# JETSON.net
KiCad netlist of a schematic drawn in Altium Designer
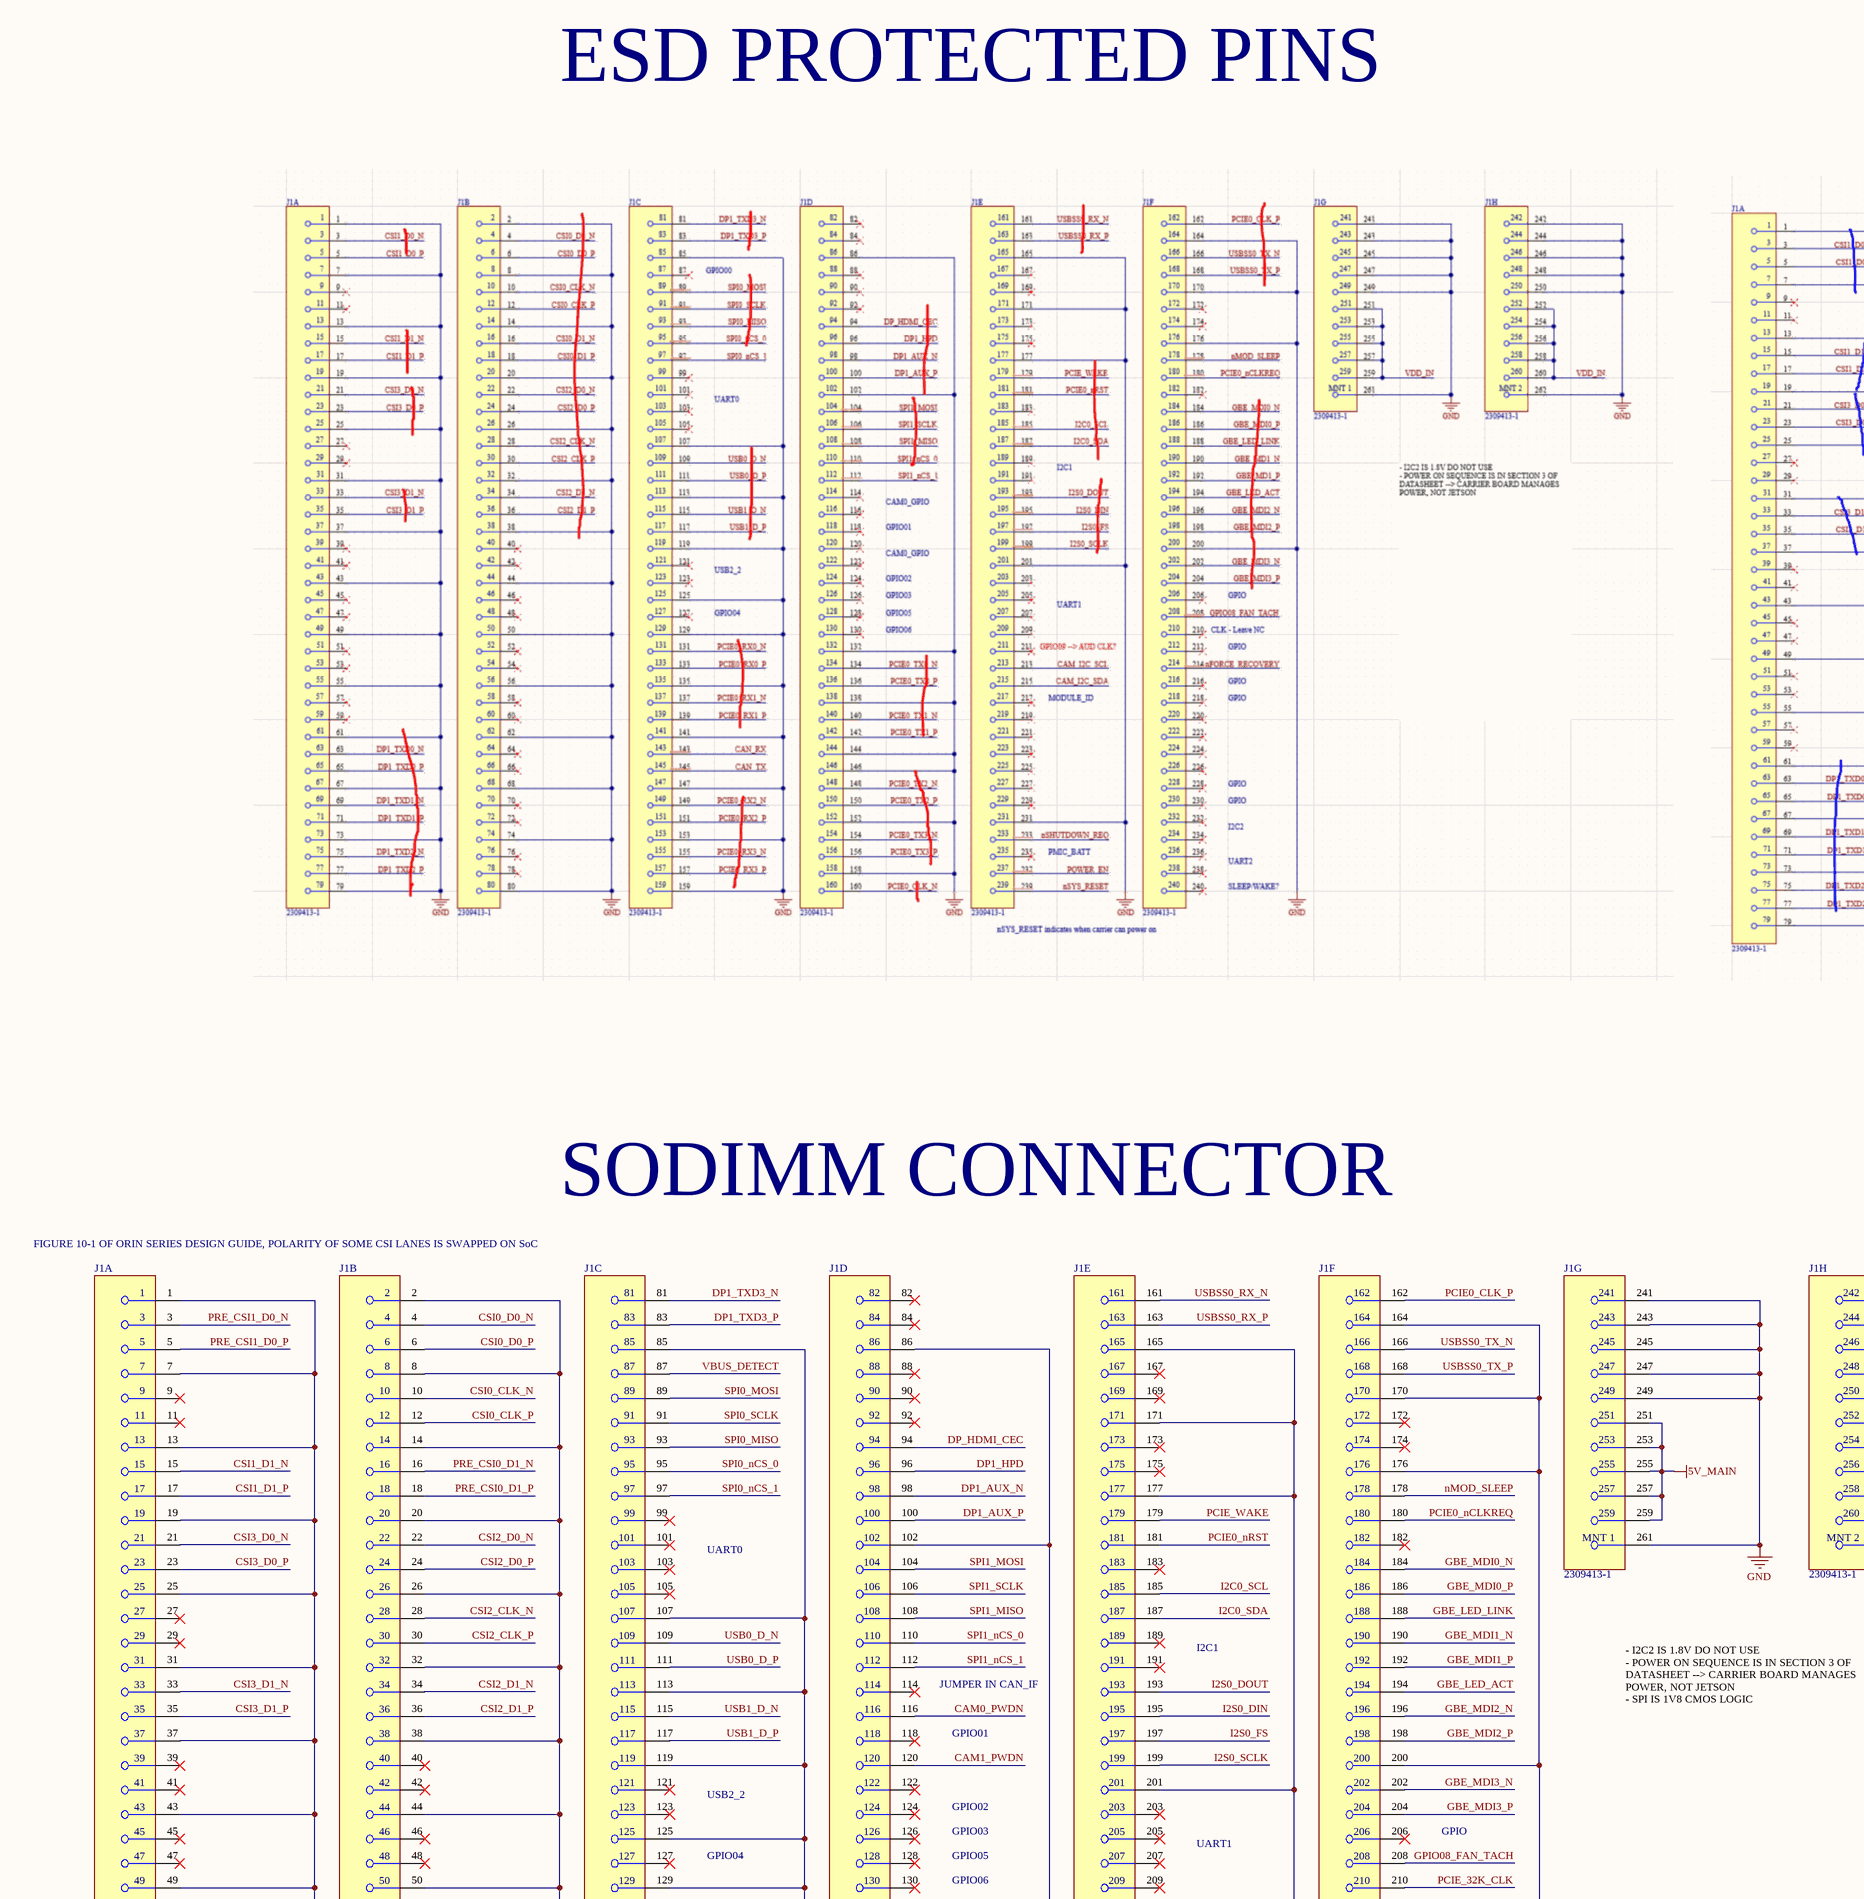
[diagram p0: JETSON.SchDoc, top left]
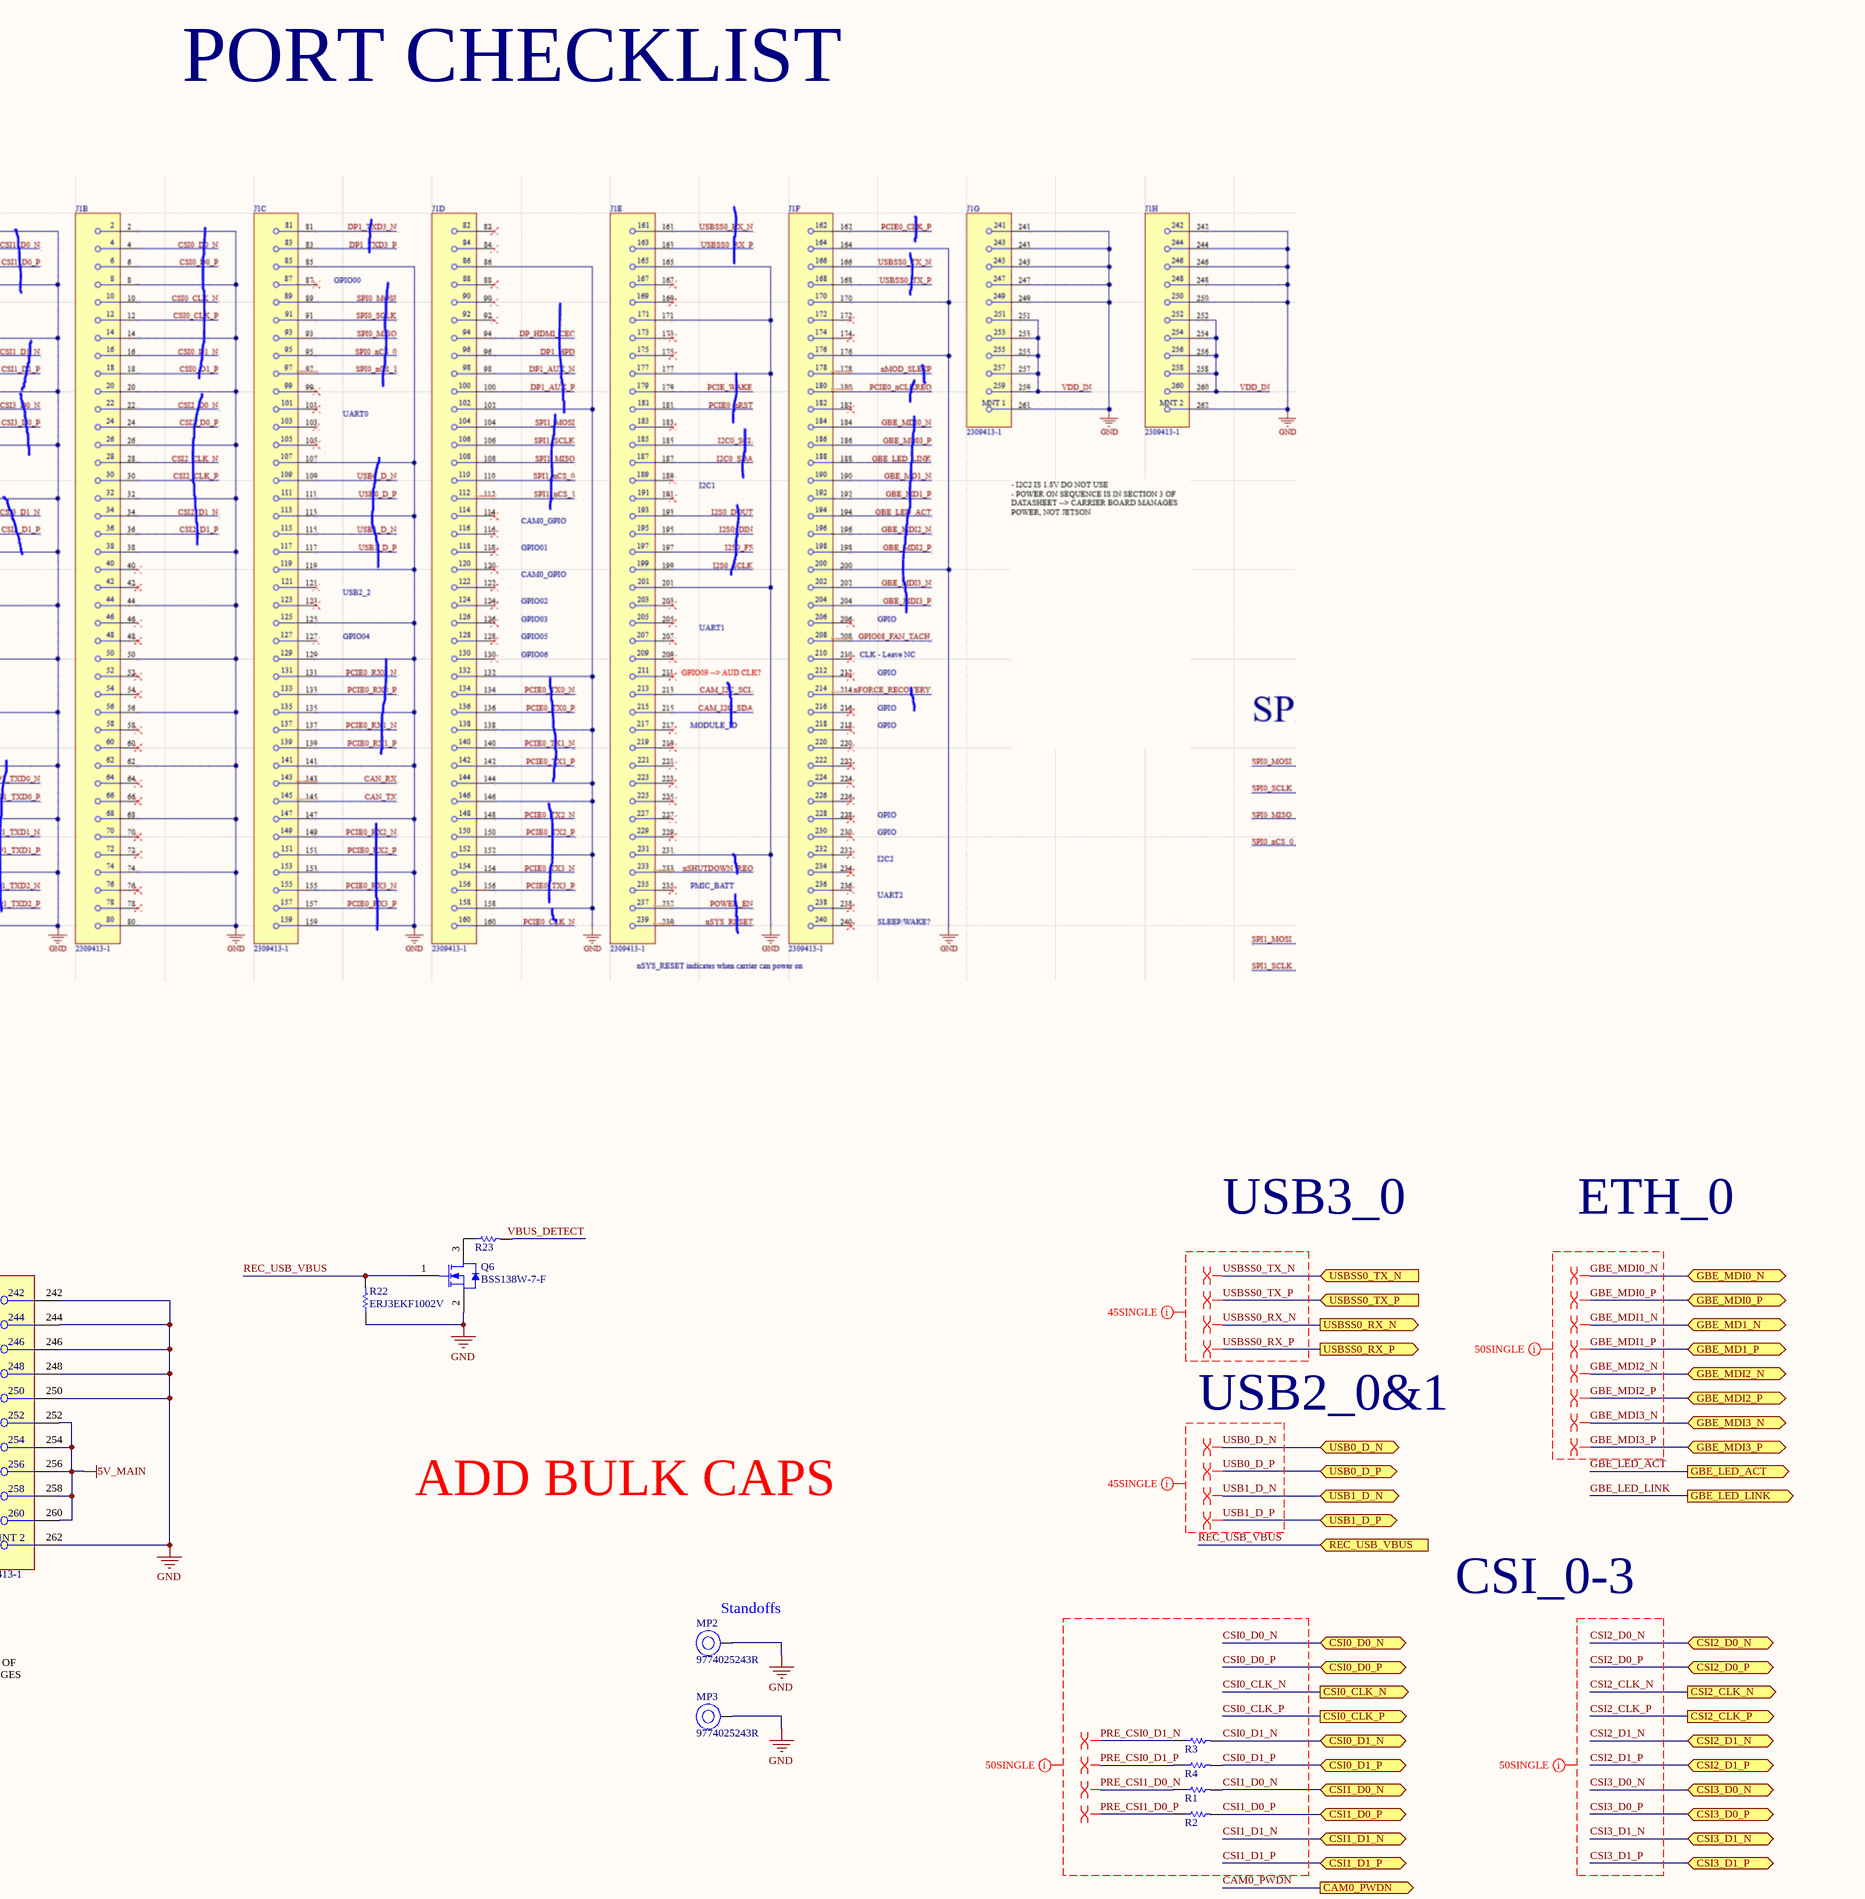
[diagram p1: JETSON.SchDoc, top right]
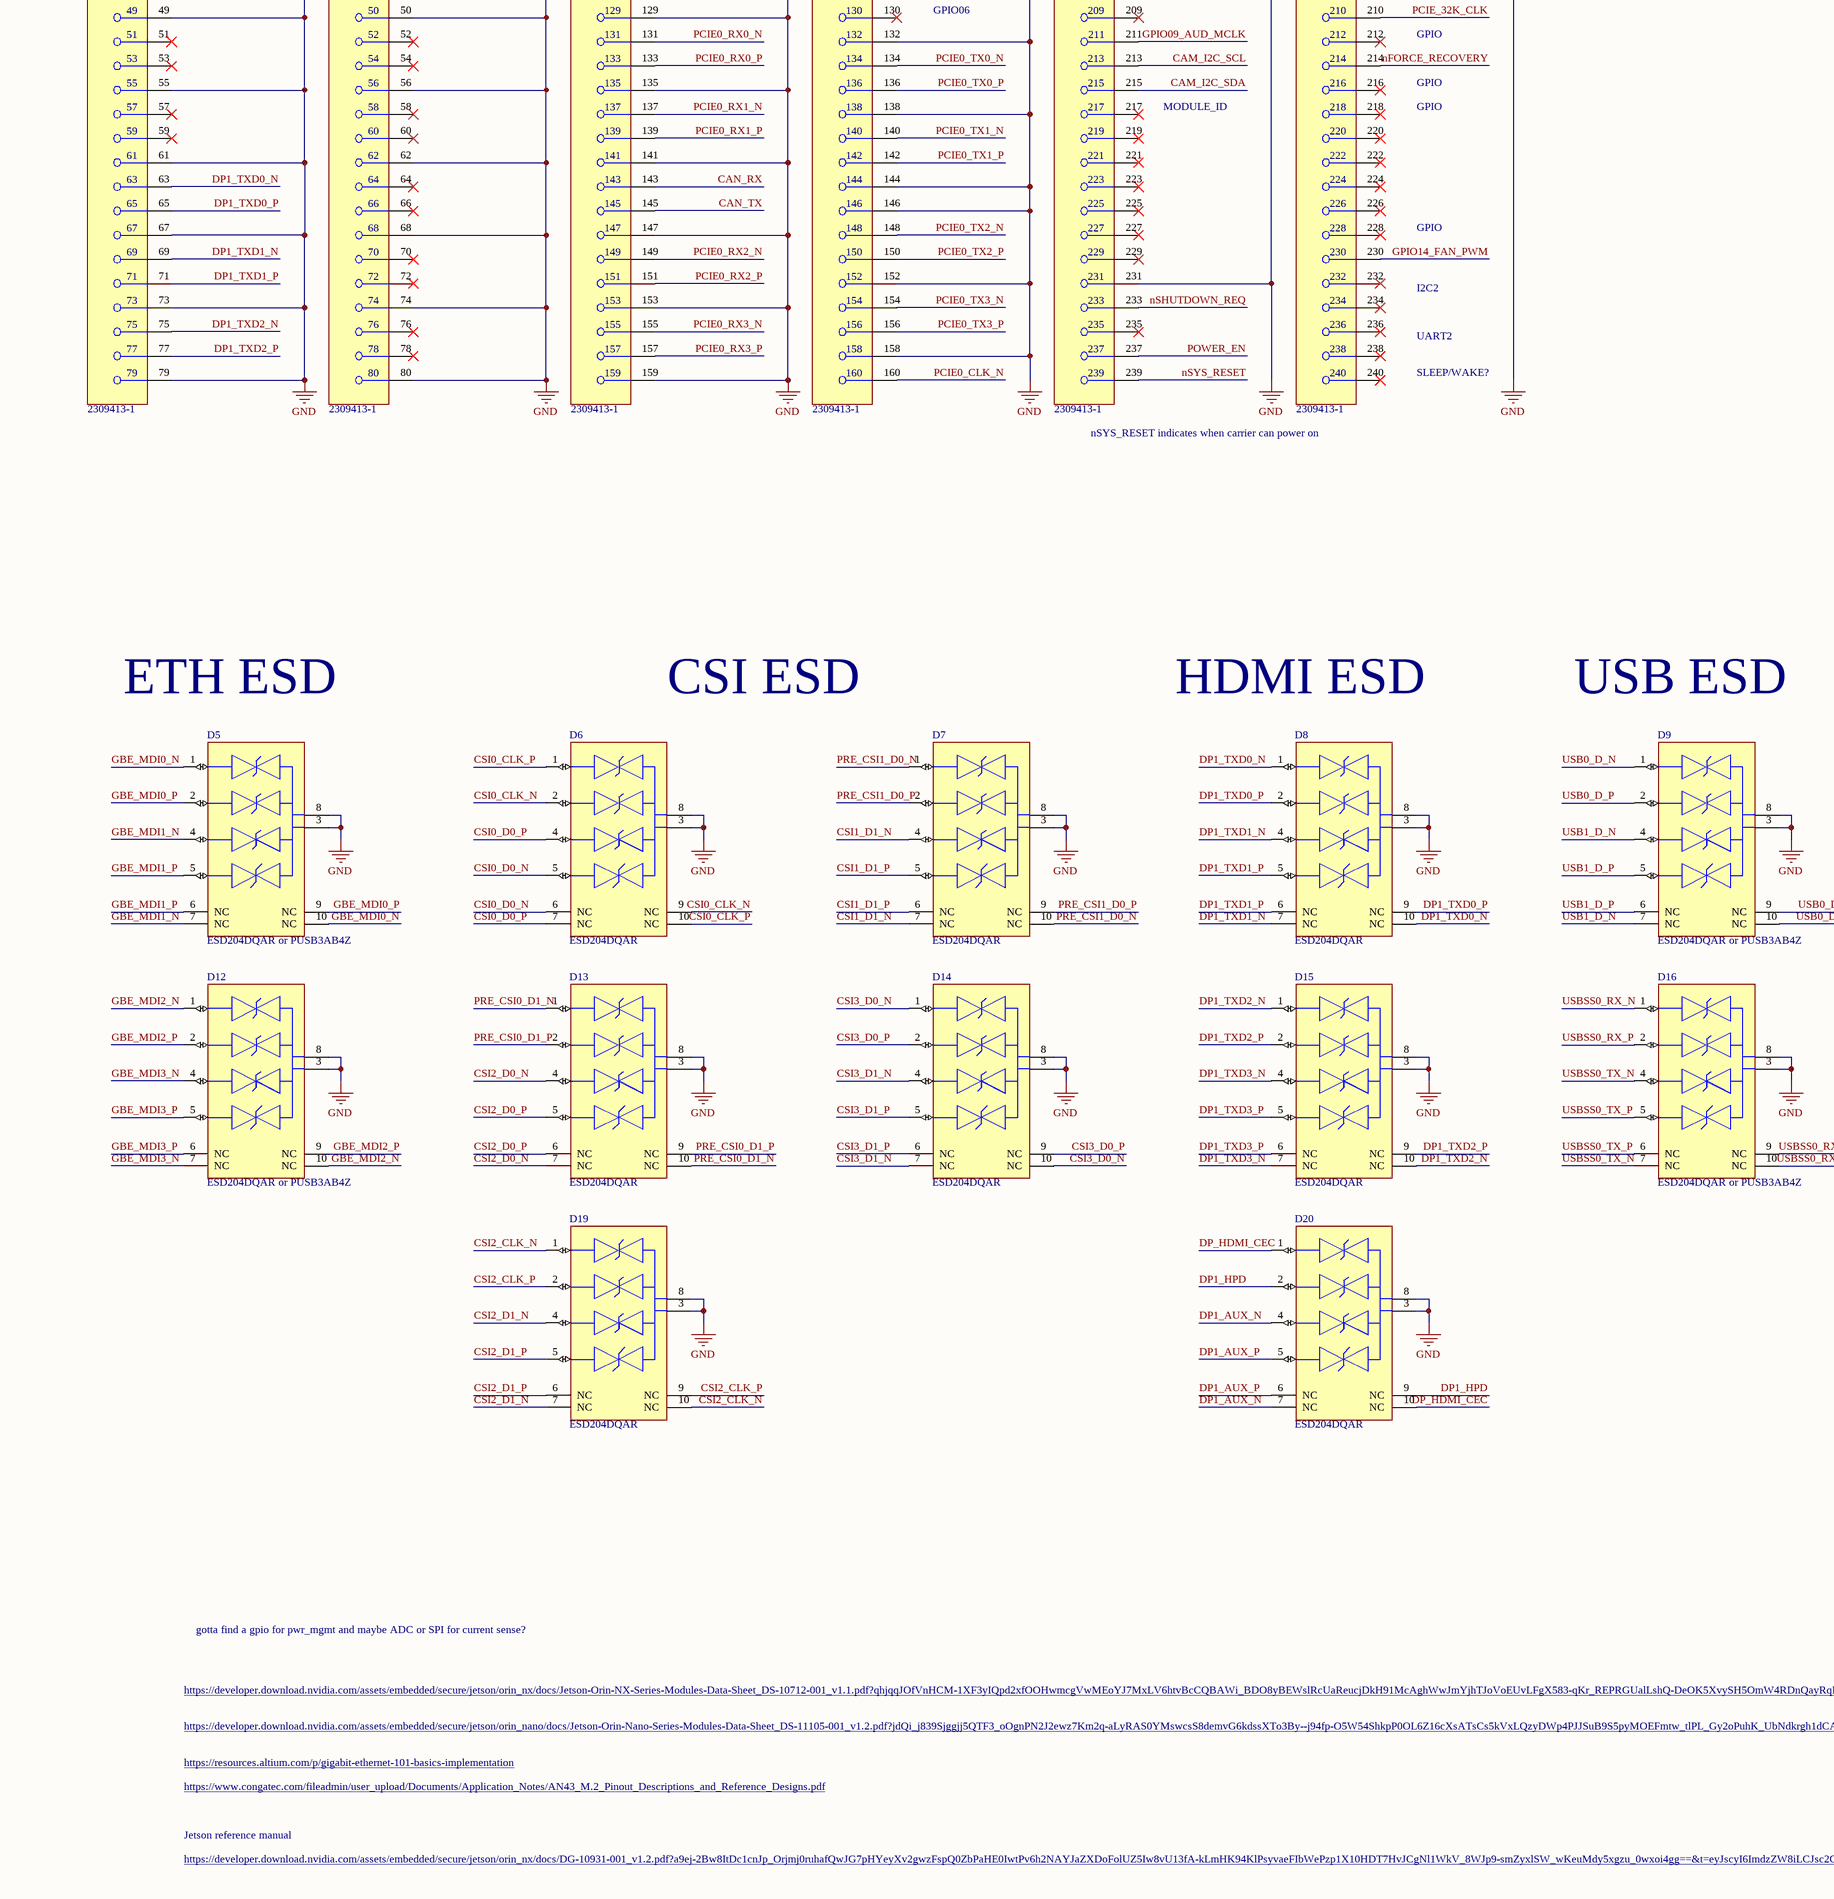
[diagram p2: JETSON.SchDoc, bottom left]
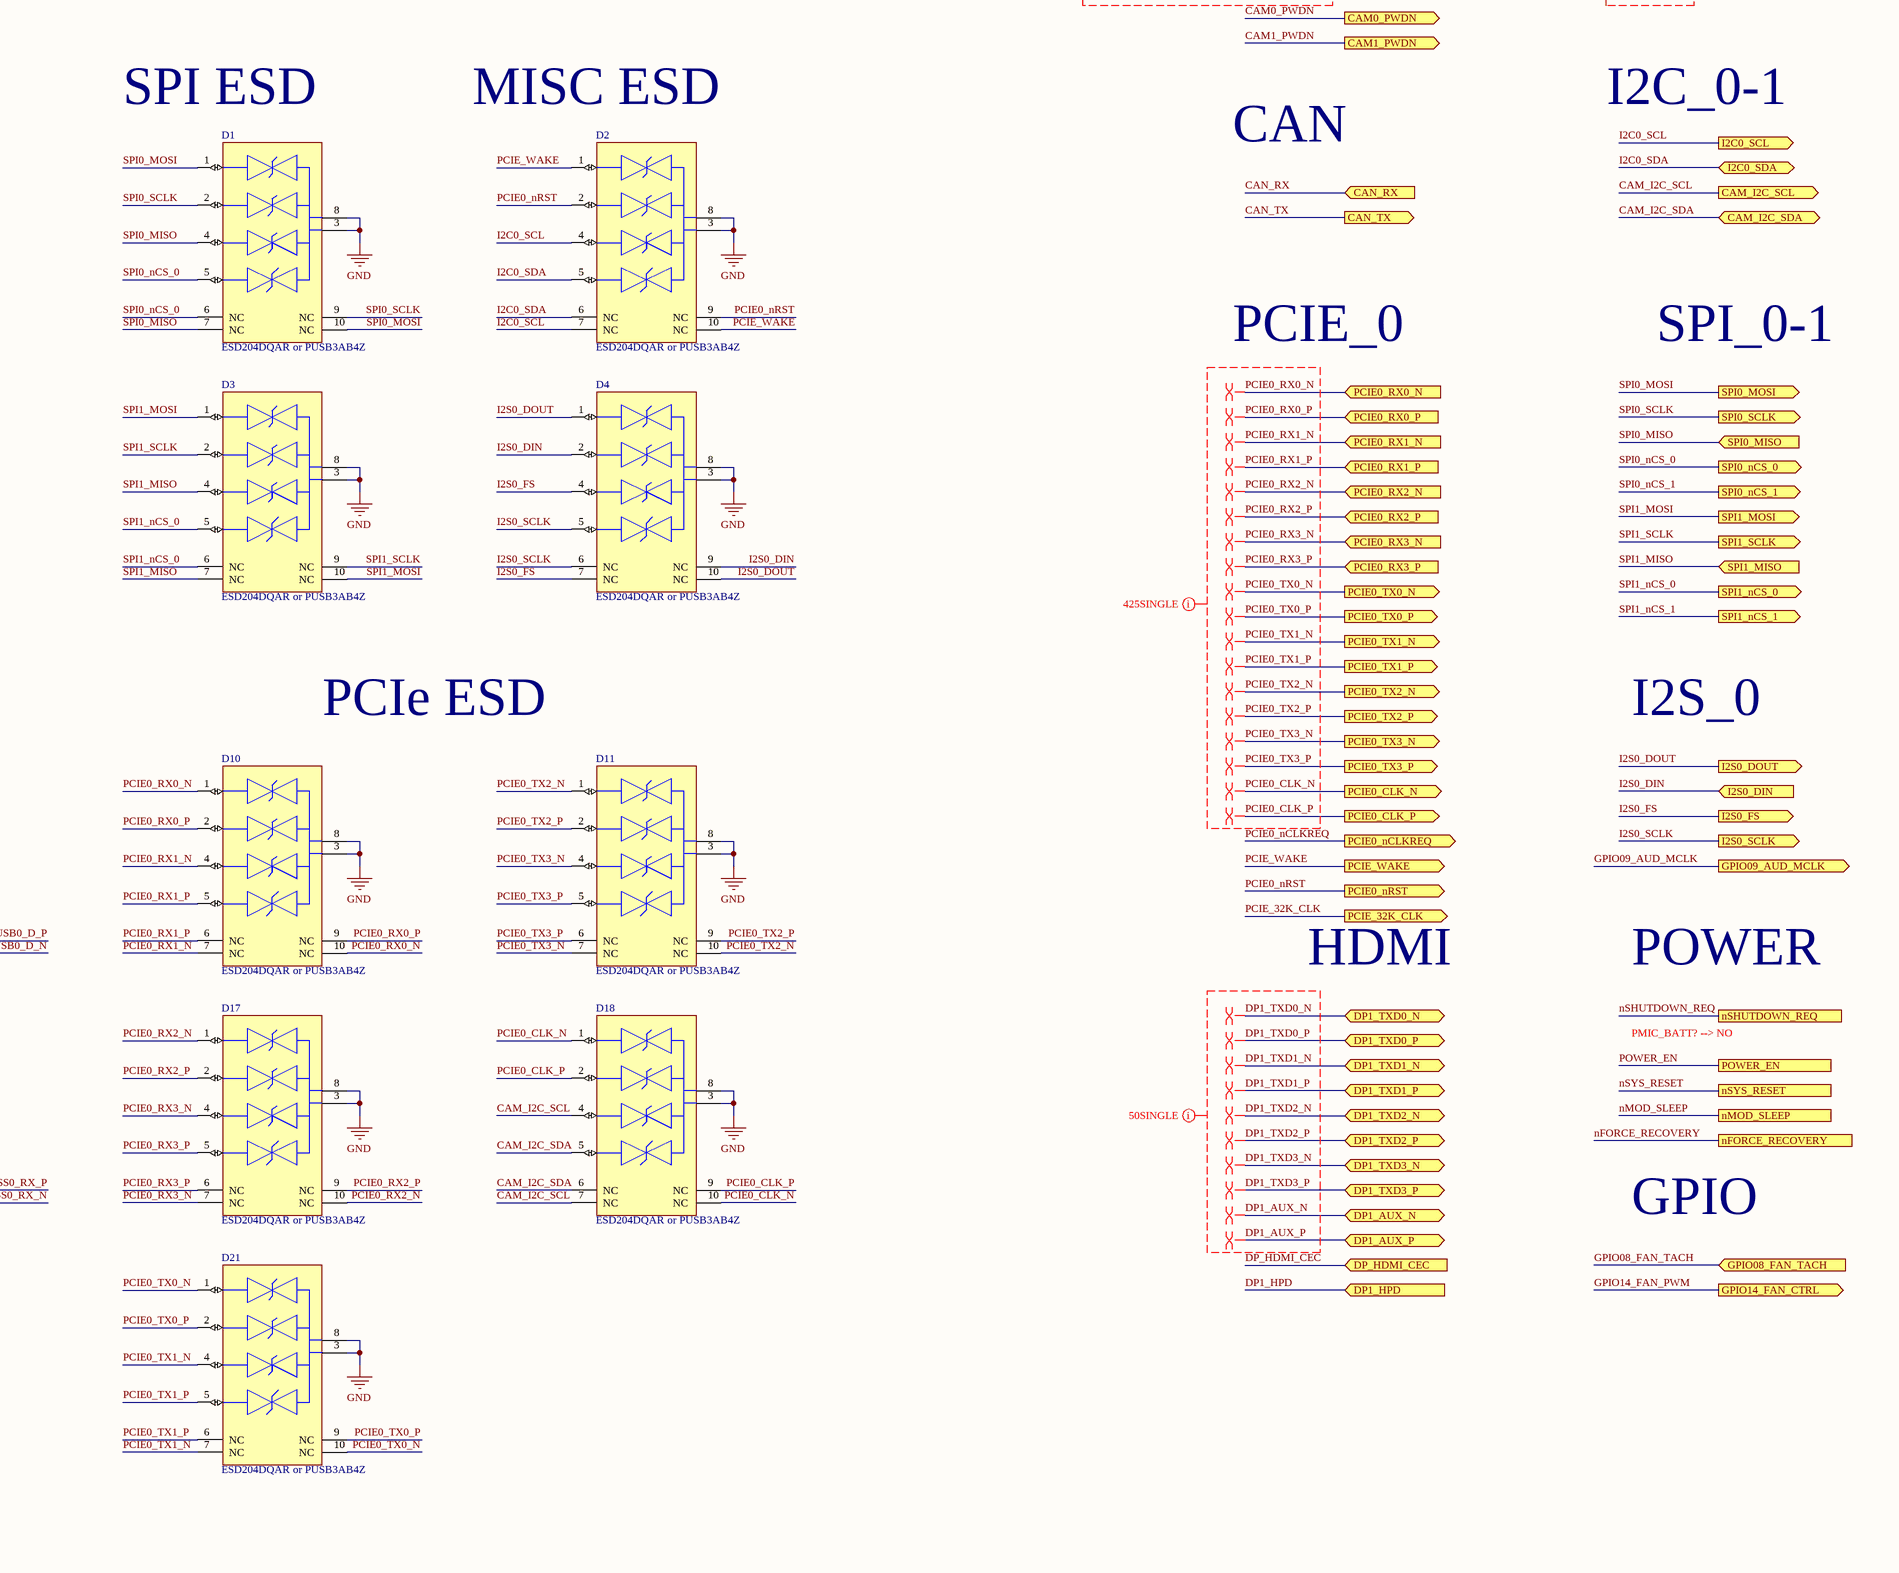
[diagram p3: JETSON.SchDoc, bottom right]

(export (version "E")
  (design (tool "Eeschema 10.0.6"))
  (components
    (comp (ref "D1")
      (value "ESD204DQAR or PUSB3AB4Z")
      (footprint "FP-DQA0010A-MFG")
      (description "4-CHANNEL LOW-CAPACITANCE SURGE")
      (fields
        (field (name "MANUFACTURER") "Texas Instruments")
        (field (name "OCTOPART") "https://octopart.com/esd204dqar-texas+instruments-89917476")
      )
      (libsource (lib "Altium Content Vault") (part "1465e58c1818c7767b55926832f0bf5"))
    )
    (comp (ref "D2")
      (value "ESD204DQAR or PUSB3AB4Z")
      (footprint "FP-DQA0010A-MFG")
      (description "4-CHANNEL LOW-CAPACITANCE SURGE")
      (fields
        (field (name "MANUFACTURER") "Texas Instruments")
        (field (name "OCTOPART") "https://octopart.com/esd204dqar-texas+instruments-89917476")
      )
      (libsource (lib "Altium Content Vault") (part "1465e58c1818c7767b55926832f0bf5"))
    )
    (comp (ref "D3")
      (value "ESD204DQAR or PUSB3AB4Z")
      (footprint "FP-DQA0010A-MFG")
      (description "4-CHANNEL LOW-CAPACITANCE SURGE")
      (fields
        (field (name "MANUFACTURER") "Texas Instruments")
        (field (name "OCTOPART") "https://octopart.com/esd204dqar-texas+instruments-89917476")
      )
      (libsource (lib "Altium Content Vault") (part "1465e58c1818c7767b55926832f0bf5"))
    )
    (comp (ref "D4")
      (value "ESD204DQAR or PUSB3AB4Z")
      (footprint "FP-DQA0010A-MFG")
      (description "4-CHANNEL LOW-CAPACITANCE SURGE")
      (fields
        (field (name "MANUFACTURER") "Texas Instruments")
        (field (name "OCTOPART") "https://octopart.com/esd204dqar-texas+instruments-89917476")
      )
      (libsource (lib "Altium Content Vault") (part "1465e58c1818c7767b55926832f0bf5"))
    )
    (comp (ref "D5")
      (value "ESD204DQAR or PUSB3AB4Z")
      (footprint "FP-DQA0010A-MFG")
      (description "4-CHANNEL LOW-CAPACITANCE SURGE")
      (fields
        (field (name "MANUFACTURER") "Texas Instruments")
        (field (name "OCTOPART") "https://octopart.com/esd204dqar-texas+instruments-89917476")
      )
      (libsource (lib "Altium Content Vault") (part "1465e58c1818c7767b55926832f0bf5"))
    )
    (comp (ref "D6")
      (value "ESD204DQAR")
      (footprint "FP-DQA0010A-MFG")
      (description "4-CHANNEL LOW-CAPACITANCE SURGE")
      (fields
        (field (name "MANUFACTURER") "Texas Instruments")
        (field (name "OCTOPART") "https://octopart.com/esd204dqar-texas+instruments-89917476")
      )
      (libsource (lib "Altium Content Vault") (part "1465e58c1818c7767b55926832f0bf5"))
    )
    (comp (ref "D7")
      (value "ESD204DQAR")
      (footprint "FP-DQA0010A-MFG")
      (description "4-CHANNEL LOW-CAPACITANCE SURGE")
      (fields
        (field (name "MANUFACTURER") "Texas Instruments")
        (field (name "OCTOPART") "https://octopart.com/esd204dqar-texas+instruments-89917476")
      )
      (libsource (lib "Altium Content Vault") (part "1465e58c1818c7767b55926832f0bf5"))
    )
    (comp (ref "D8")
      (value "ESD204DQAR")
      (footprint "FP-DQA0010A-MFG")
      (description "4-CHANNEL LOW-CAPACITANCE SURGE")
      (fields
        (field (name "MANUFACTURER") "Texas Instruments")
        (field (name "OCTOPART") "https://octopart.com/esd204dqar-texas+instruments-89917476")
      )
      (libsource (lib "Altium Content Vault") (part "1465e58c1818c7767b55926832f0bf5"))
    )
    (comp (ref "D9")
      (value "ESD204DQAR or PUSB3AB4Z")
      (footprint "FP-DQA0010A-MFG")
      (description "4-CHANNEL LOW-CAPACITANCE SURGE")
      (fields
        (field (name "MANUFACTURER") "Texas Instruments")
        (field (name "OCTOPART") "https://octopart.com/esd204dqar-texas+instruments-89917476")
      )
      (libsource (lib "Altium Content Vault") (part "1465e58c1818c7767b55926832f0bf5"))
    )
    (comp (ref "D10")
      (value "ESD204DQAR or PUSB3AB4Z")
      (footprint "FP-DQA0010A-MFG")
      (description "4-CHANNEL LOW-CAPACITANCE SURGE")
      (fields
        (field (name "MANUFACTURER") "Texas Instruments")
        (field (name "OCTOPART") "https://octopart.com/esd204dqar-texas+instruments-89917476")
      )
      (libsource (lib "Altium Content Vault") (part "1465e58c1818c7767b55926832f0bf5"))
    )
    (comp (ref "D11")
      (value "ESD204DQAR or PUSB3AB4Z")
      (footprint "FP-DQA0010A-MFG")
      (description "4-CHANNEL LOW-CAPACITANCE SURGE")
      (fields
        (field (name "MANUFACTURER") "Texas Instruments")
        (field (name "OCTOPART") "https://octopart.com/esd204dqar-texas+instruments-89917476")
      )
      (libsource (lib "Altium Content Vault") (part "1465e58c1818c7767b55926832f0bf5"))
    )
    (comp (ref "D12")
      (value "ESD204DQAR or PUSB3AB4Z")
      (footprint "FP-DQA0010A-MFG")
      (description "4-CHANNEL LOW-CAPACITANCE SURGE")
      (fields
        (field (name "MANUFACTURER") "Texas Instruments")
        (field (name "OCTOPART") "https://octopart.com/esd204dqar-texas+instruments-89917476")
      )
      (libsource (lib "Altium Content Vault") (part "1465e58c1818c7767b55926832f0bf5"))
    )
    (comp (ref "D13")
      (value "ESD204DQAR")
      (footprint "FP-DQA0010A-MFG")
      (description "4-CHANNEL LOW-CAPACITANCE SURGE")
      (fields
        (field (name "MANUFACTURER") "Texas Instruments")
        (field (name "OCTOPART") "https://octopart.com/esd204dqar-texas+instruments-89917476")
      )
      (libsource (lib "Altium Content Vault") (part "1465e58c1818c7767b55926832f0bf5"))
    )
    (comp (ref "D14")
      (value "ESD204DQAR")
      (footprint "FP-DQA0010A-MFG")
      (description "4-CHANNEL LOW-CAPACITANCE SURGE")
      (fields
        (field (name "MANUFACTURER") "Texas Instruments")
        (field (name "OCTOPART") "https://octopart.com/esd204dqar-texas+instruments-89917476")
      )
      (libsource (lib "Altium Content Vault") (part "1465e58c1818c7767b55926832f0bf5"))
    )
    (comp (ref "D15")
      (value "ESD204DQAR")
      (footprint "FP-DQA0010A-MFG")
      (description "4-CHANNEL LOW-CAPACITANCE SURGE")
      (fields
        (field (name "MANUFACTURER") "Texas Instruments")
        (field (name "OCTOPART") "https://octopart.com/esd204dqar-texas+instruments-89917476")
      )
      (libsource (lib "Altium Content Vault") (part "1465e58c1818c7767b55926832f0bf5"))
    )
    (comp (ref "D16")
      (value "ESD204DQAR or PUSB3AB4Z")
      (footprint "FP-DQA0010A-MFG")
      (description "4-CHANNEL LOW-CAPACITANCE SURGE")
      (fields
        (field (name "MANUFACTURER") "Texas Instruments")
        (field (name "OCTOPART") "https://octopart.com/esd204dqar-texas+instruments-89917476")
      )
      (libsource (lib "Altium Content Vault") (part "1465e58c1818c7767b55926832f0bf5"))
    )
    (comp (ref "D17")
      (value "ESD204DQAR or PUSB3AB4Z")
      (footprint "FP-DQA0010A-MFG")
      (description "4-CHANNEL LOW-CAPACITANCE SURGE")
      (fields
        (field (name "MANUFACTURER") "Texas Instruments")
        (field (name "OCTOPART") "https://octopart.com/esd204dqar-texas+instruments-89917476")
      )
      (libsource (lib "Altium Content Vault") (part "1465e58c1818c7767b55926832f0bf5"))
    )
    (comp (ref "D18")
      (value "ESD204DQAR or PUSB3AB4Z")
      (footprint "FP-DQA0010A-MFG")
      (description "4-CHANNEL LOW-CAPACITANCE SURGE")
      (fields
        (field (name "MANUFACTURER") "Texas Instruments")
        (field (name "OCTOPART") "https://octopart.com/esd204dqar-texas+instruments-89917476")
      )
      (libsource (lib "Altium Content Vault") (part "1465e58c1818c7767b55926832f0bf5"))
    )
    (comp (ref "D19")
      (value "ESD204DQAR")
      (footprint "FP-DQA0010A-MFG")
      (description "4-CHANNEL LOW-CAPACITANCE SURGE")
      (fields
        (field (name "MANUFACTURER") "Texas Instruments")
        (field (name "OCTOPART") "https://octopart.com/esd204dqar-texas+instruments-89917476")
      )
      (libsource (lib "Altium Content Vault") (part "1465e58c1818c7767b55926832f0bf5"))
    )
    (comp (ref "D20")
      (value "ESD204DQAR")
      (footprint "FP-DQA0010A-MFG")
      (description "4-CHANNEL LOW-CAPACITANCE SURGE")
      (fields
        (field (name "MANUFACTURER") "Texas Instruments")
        (field (name "OCTOPART") "https://octopart.com/esd204dqar-texas+instruments-89917476")
      )
      (libsource (lib "Altium Content Vault") (part "1465e58c1818c7767b55926832f0bf5"))
    )
    (comp (ref "D21")
      (value "ESD204DQAR or PUSB3AB4Z")
      (footprint "FP-DQA0010A-MFG")
      (description "4-CHANNEL LOW-CAPACITANCE SURGE")
      (fields
        (field (name "MANUFACTURER") "Texas Instruments")
        (field (name "OCTOPART") "https://octopart.com/esd204dqar-texas+instruments-89917476")
      )
      (libsource (lib "Altium Content Vault") (part "1465e58c1818c7767b55926832f0bf5"))
    )
    (comp (ref "J1")
      (value "2309413-1")
      (footprint "FP-2309413-1-MFG")
      (description "DDR4 SODIMM 260P 9.2H STD")
      (fields
        (field (name "OCTOPART") "https://octopart.com/2309413-1-te+connectivity-84799194")
        (field (name "MANUFACTURER") "TE Connectivity")
      )
      (libsource (lib "Altium Content Vault") (part "4d1075b24ee2591bdcd47d674b3d2aa"))
    )
    (comp (ref "MP2")
      (value "9774025243R")
      (footprint "9774025243")
      (description "9774025243R Spacer Material: Steel, Tin-Plated Mounting: SMT Series: WA-SMST Thread D: M2")
      (libsource (lib "Altium Content Vault") (part "Spacer"))
    )
    (comp (ref "MP3")
      (value "9774025243R")
      (footprint "9774025243")
      (description "9774025243R Spacer Material: Steel, Tin-Plated Mounting: SMT Series: WA-SMST Thread D: M2")
      (libsource (lib "Altium Content Vault") (part "Spacer"))
    )
    (comp (ref "Q6")
      (value "BSS138W-7-F")
      (footprint "DIOD-SOT323-3_V")
      (fields (field (name "MANUFACTURER") "DiodesIncorporated"))
      (libsource (lib "Altium Content Vault") (part "NEMOS-GSD-3"))
    )
    (comp (ref "R1")
      (value "0402 JUMPER 0 OHM")
      (footprint "RESC1005X40X25NL05T05")
      (description "READ THE NAME")
      (libsource (lib "uORocketry Hardware") (part "RES"))
    )
    (comp (ref "R2")
      (value "0402 JUMPER 0 OHM")
      (footprint "RESC1005X40X25NL05T05")
      (description "READ THE NAME")
      (libsource (lib "uORocketry Hardware") (part "RES"))
    )
    (comp (ref "R3")
      (value "0402 JUMPER 0 OHM")
      (footprint "RESC1005X40X25NL05T05")
      (description "READ THE NAME")
      (libsource (lib "uORocketry Hardware") (part "RES"))
    )
    (comp (ref "R4")
      (value "0402 JUMPER 0 OHM")
      (footprint "RESC1005X40X25NL05T05")
      (description "READ THE NAME")
      (libsource (lib "uORocketry Hardware") (part "RES"))
    )
    (comp (ref "R22")
      (value "ERJ3EKF1002V")
      (footprint "RESC1609X55X30LL15T15")
      (description "Chip Resistor, 10 KOhm, +/- 1%, 0.1 W, -55 to 155 degC, 0603 (1608 Metric), RoHS, Tape and Reel")
      (fields (field (name "TOLERANCE") "1%") (field (name "MANUFACTURER") "Panasonic"))
      (libsource (lib "Altium Content Vault") (part "RES-2"))
    )
    (comp (ref "R23")
      (value "0402 JUMPER 0 OHM")
      (footprint "RESC1005X40X25NL05T05")
      (description "READ THE NAME")
      (libsource (lib "uORocketry Hardware") (part "RES"))
    )
  )
  (nets
    (net (code "1") (name "/CAM0_PWDN") (class "Default")
      (node (ref "J1") (pin "116") (pinfunction "116_116") (pintype "passive"))
    )
    (net (code "2") (name "/CAM1_PWDN") (class "Default")
      (node (ref "J1") (pin "120") (pinfunction "120_120") (pintype "passive"))
    )
    (net (code "3") (name "/CAM_I2C_SCL") (class "Default")
      (node (ref "D18") (pin "4") (pinfunction "IO3_4") (pintype "bidirectional"))
      (node (ref "D18") (pin "7") (pinfunction "NC_7") (pintype "passive"))
      (node (ref "J1") (pin "213") (pinfunction "213_213") (pintype "passive"))
    )
    (net (code "4") (name "/CAM_I2C_SDA") (class "Default")
      (node (ref "D18") (pin "5") (pinfunction "IO4_5") (pintype "bidirectional"))
      (node (ref "D18") (pin "6") (pinfunction "NC_6") (pintype "passive"))
      (node (ref "J1") (pin "215") (pinfunction "215_215") (pintype "passive"))
    )
    (net (code "5") (name "/CAN_RX") (class "Default")
      (node (ref "J1") (pin "143") (pinfunction "143_143") (pintype "passive"))
    )
    (net (code "6") (name "/CAN_TX") (class "Default")
      (node (ref "J1") (pin "145") (pinfunction "145_145") (pintype "passive"))
    )
    (net (code "7") (name "/CSI0_CLK_N") (class "Default")
      (node (ref "D6") (pin "2") (pinfunction "IO2_2") (pintype "bidirectional"))
      (node (ref "D6") (pin "9") (pinfunction "NC_9") (pintype "passive"))
      (node (ref "J1") (pin "10") (pinfunction "10_10") (pintype "passive"))
    )
    (net (code "8") (name "/CSI0_CLK_P") (class "Default")
      (node (ref "D6") (pin "1") (pinfunction "IO1_1") (pintype "bidirectional"))
      (node (ref "D6") (pin "10") (pinfunction "NC_10") (pintype "passive"))
      (node (ref "J1") (pin "12") (pinfunction "12_12") (pintype "passive"))
    )
    (net (code "9") (name "/CSI0_D0_N") (class "Default")
      (node (ref "D6") (pin "5") (pinfunction "IO4_5") (pintype "bidirectional"))
      (node (ref "D6") (pin "6") (pinfunction "NC_6") (pintype "passive"))
      (node (ref "J1") (pin "4") (pinfunction "4_4") (pintype "passive"))
    )
    (net (code "10") (name "/CSI0_D0_P") (class "Default")
      (node (ref "D6") (pin "4") (pinfunction "IO3_4") (pintype "bidirectional"))
      (node (ref "D6") (pin "7") (pinfunction "NC_7") (pintype "passive"))
      (node (ref "J1") (pin "6") (pinfunction "6_6") (pintype "passive"))
    )
    (net (code "11") (name "/CSI0_D1_N") (class "Default")
      (node (ref "R3") (pin "2") (pinfunction "2_2") (pintype "passive"))
    )
    (net (code "12") (name "/CSI0_D1_P") (class "Default")
      (node (ref "R4") (pin "2") (pinfunction "2_2") (pintype "passive"))
    )
    (net (code "13") (name "/CSI1_D0_N") (class "Default")
      (node (ref "R1") (pin "2") (pinfunction "2_2") (pintype "passive"))
    )
    (net (code "14") (name "/CSI1_D0_P") (class "Default")
      (node (ref "R2") (pin "2") (pinfunction "2_2") (pintype "passive"))
    )
    (net (code "15") (name "/CSI1_D1_N") (class "Default")
      (node (ref "D7") (pin "4") (pinfunction "IO3_4") (pintype "bidirectional"))
      (node (ref "D7") (pin "7") (pinfunction "NC_7") (pintype "passive"))
      (node (ref "J1") (pin "15") (pinfunction "15_15") (pintype "passive"))
    )
    (net (code "16") (name "/CSI1_D1_P") (class "Default")
      (node (ref "D7") (pin "5") (pinfunction "IO4_5") (pintype "bidirectional"))
      (node (ref "D7") (pin "6") (pinfunction "NC_6") (pintype "passive"))
      (node (ref "J1") (pin "17") (pinfunction "17_17") (pintype "passive"))
    )
    (net (code "17") (name "/CSI2_CLK_N") (class "Default")
      (node (ref "D19") (pin "1") (pinfunction "IO1_1") (pintype "bidirectional"))
      (node (ref "D19") (pin "10") (pinfunction "NC_10") (pintype "passive"))
      (node (ref "J1") (pin "28") (pinfunction "28_28") (pintype "passive"))
    )
    (net (code "18") (name "/CSI2_CLK_P") (class "Default")
      (node (ref "D19") (pin "2") (pinfunction "IO2_2") (pintype "bidirectional"))
      (node (ref "D19") (pin "9") (pinfunction "NC_9") (pintype "passive"))
      (node (ref "J1") (pin "30") (pinfunction "30_30") (pintype "passive"))
    )
    (net (code "19") (name "/CSI2_D0_N") (class "Default")
      (node (ref "D13") (pin "4") (pinfunction "IO3_4") (pintype "bidirectional"))
      (node (ref "D13") (pin "7") (pinfunction "NC_7") (pintype "passive"))
      (node (ref "J1") (pin "22") (pinfunction "22_22") (pintype "passive"))
    )
    (net (code "20") (name "/CSI2_D0_P") (class "Default")
      (node (ref "D13") (pin "5") (pinfunction "IO4_5") (pintype "bidirectional"))
      (node (ref "D13") (pin "6") (pinfunction "NC_6") (pintype "passive"))
      (node (ref "J1") (pin "24") (pinfunction "24_24") (pintype "passive"))
    )
    (net (code "21") (name "/CSI2_D1_N") (class "Default")
      (node (ref "D19") (pin "4") (pinfunction "IO3_4") (pintype "bidirectional"))
      (node (ref "D19") (pin "7") (pinfunction "NC_7") (pintype "passive"))
      (node (ref "J1") (pin "34") (pinfunction "34_34") (pintype "passive"))
    )
    (net (code "22") (name "/CSI2_D1_P") (class "Default")
      (node (ref "D19") (pin "5") (pinfunction "IO4_5") (pintype "bidirectional"))
      (node (ref "D19") (pin "6") (pinfunction "NC_6") (pintype "passive"))
      (node (ref "J1") (pin "36") (pinfunction "36_36") (pintype "passive"))
    )
    (net (code "23") (name "/CSI3_D0_N") (class "Default")
      (node (ref "D14") (pin "1") (pinfunction "IO1_1") (pintype "bidirectional"))
      (node (ref "D14") (pin "10") (pinfunction "NC_10") (pintype "passive"))
      (node (ref "J1") (pin "21") (pinfunction "21_21") (pintype "passive"))
    )
    (net (code "24") (name "/CSI3_D0_P") (class "Default")
      (node (ref "D14") (pin "2") (pinfunction "IO2_2") (pintype "bidirectional"))
      (node (ref "D14") (pin "9") (pinfunction "NC_9") (pintype "passive"))
      (node (ref "J1") (pin "23") (pinfunction "23_23") (pintype "passive"))
    )
    (net (code "25") (name "/CSI3_D1_N") (class "Default")
      (node (ref "D14") (pin "4") (pinfunction "IO3_4") (pintype "bidirectional"))
      (node (ref "D14") (pin "7") (pinfunction "NC_7") (pintype "passive"))
      (node (ref "J1") (pin "33") (pinfunction "33_33") (pintype "passive"))
    )
    (net (code "26") (name "/CSI3_D1_P") (class "Default")
      (node (ref "D14") (pin "5") (pinfunction "IO4_5") (pintype "bidirectional"))
      (node (ref "D14") (pin "6") (pinfunction "NC_6") (pintype "passive"))
      (node (ref "J1") (pin "35") (pinfunction "35_35") (pintype "passive"))
    )
    (net (code "27") (name "/DP1_AUX_N") (class "Default")
      (node (ref "D20") (pin "4") (pinfunction "IO3_4") (pintype "bidirectional"))
      (node (ref "D20") (pin "7") (pinfunction "NC_7") (pintype "passive"))
      (node (ref "J1") (pin "98") (pinfunction "98_98") (pintype "passive"))
    )
    (net (code "28") (name "/DP1_AUX_P") (class "Default")
      (node (ref "D20") (pin "5") (pinfunction "IO4_5") (pintype "bidirectional"))
      (node (ref "D20") (pin "6") (pinfunction "NC_6") (pintype "passive"))
      (node (ref "J1") (pin "100") (pinfunction "100_100") (pintype "passive"))
    )
    (net (code "29") (name "/DP1_HPD") (class "Default")
      (node (ref "D20") (pin "2") (pinfunction "IO2_2") (pintype "bidirectional"))
      (node (ref "D20") (pin "9") (pinfunction "NC_9") (pintype "passive"))
      (node (ref "J1") (pin "96") (pinfunction "96_96") (pintype "passive"))
    )
    (net (code "30") (name "/DP1_TXD0_N") (class "Default")
      (node (ref "D8") (pin "1") (pinfunction "IO1_1") (pintype "bidirectional"))
      (node (ref "D8") (pin "10") (pinfunction "NC_10") (pintype "passive"))
      (node (ref "J1") (pin "63") (pinfunction "63_63") (pintype "passive"))
    )
    (net (code "31") (name "/DP1_TXD0_P") (class "Default")
      (node (ref "D8") (pin "2") (pinfunction "IO2_2") (pintype "bidirectional"))
      (node (ref "D8") (pin "9") (pinfunction "NC_9") (pintype "passive"))
      (node (ref "J1") (pin "65") (pinfunction "65_65") (pintype "passive"))
    )
    (net (code "32") (name "/DP1_TXD1_N") (class "Default")
      (node (ref "D8") (pin "4") (pinfunction "IO3_4") (pintype "bidirectional"))
      (node (ref "D8") (pin "7") (pinfunction "NC_7") (pintype "passive"))
      (node (ref "J1") (pin "69") (pinfunction "69_69") (pintype "passive"))
    )
    (net (code "33") (name "/DP1_TXD1_P") (class "Default")
      (node (ref "D8") (pin "5") (pinfunction "IO4_5") (pintype "bidirectional"))
      (node (ref "D8") (pin "6") (pinfunction "NC_6") (pintype "passive"))
      (node (ref "J1") (pin "71") (pinfunction "71_71") (pintype "passive"))
    )
    (net (code "34") (name "/DP1_TXD2_N") (class "Default")
      (node (ref "D15") (pin "1") (pinfunction "IO1_1") (pintype "bidirectional"))
      (node (ref "D15") (pin "10") (pinfunction "NC_10") (pintype "passive"))
      (node (ref "J1") (pin "75") (pinfunction "75_75") (pintype "passive"))
    )
    (net (code "35") (name "/DP1_TXD2_P") (class "Default")
      (node (ref "D15") (pin "2") (pinfunction "IO2_2") (pintype "bidirectional"))
      (node (ref "D15") (pin "9") (pinfunction "NC_9") (pintype "passive"))
      (node (ref "J1") (pin "77") (pinfunction "77_77") (pintype "passive"))
    )
    (net (code "36") (name "/DP1_TXD3_N") (class "Default")
      (node (ref "D15") (pin "4") (pinfunction "IO3_4") (pintype "bidirectional"))
      (node (ref "D15") (pin "7") (pinfunction "NC_7") (pintype "passive"))
      (node (ref "J1") (pin "81") (pinfunction "81_81") (pintype "passive"))
    )
    (net (code "37") (name "/DP1_TXD3_P") (class "Default")
      (node (ref "D15") (pin "5") (pinfunction "IO4_5") (pintype "bidirectional"))
      (node (ref "D15") (pin "6") (pinfunction "NC_6") (pintype "passive"))
      (node (ref "J1") (pin "83") (pinfunction "83_83") (pintype "passive"))
    )
    (net (code "38") (name "/DP_HDMI_CEC") (class "Default")
      (node (ref "D20") (pin "1") (pinfunction "IO1_1") (pintype "bidirectional"))
      (node (ref "D20") (pin "10") (pinfunction "NC_10") (pintype "passive"))
      (node (ref "J1") (pin "94") (pinfunction "94_94") (pintype "passive"))
    )
    (net (code "39") (name "/GBE_LED_ACT") (class "Default")
      (node (ref "J1") (pin "194") (pinfunction "194_194") (pintype "passive"))
    )
    (net (code "40") (name "/GBE_LED_LINK") (class "Default")
      (node (ref "J1") (pin "188") (pinfunction "188_188") (pintype "passive"))
    )
    (net (code "41") (name "/GBE_MDI0_N") (class "Default")
      (node (ref "D5") (pin "1") (pinfunction "IO1_1") (pintype "bidirectional"))
      (node (ref "D5") (pin "10") (pinfunction "NC_10") (pintype "passive"))
      (node (ref "J1") (pin "184") (pinfunction "184_184") (pintype "passive"))
    )
    (net (code "42") (name "/GBE_MDI0_P") (class "Default")
      (node (ref "D5") (pin "2") (pinfunction "IO2_2") (pintype "bidirectional"))
      (node (ref "D5") (pin "9") (pinfunction "NC_9") (pintype "passive"))
      (node (ref "J1") (pin "186") (pinfunction "186_186") (pintype "passive"))
    )
    (net (code "43") (name "/GBE_MDI1_N") (class "Default")
      (node (ref "D5") (pin "4") (pinfunction "IO3_4") (pintype "bidirectional"))
      (node (ref "D5") (pin "7") (pinfunction "NC_7") (pintype "passive"))
      (node (ref "J1") (pin "190") (pinfunction "190_190") (pintype "passive"))
    )
    (net (code "44") (name "/GBE_MDI1_P") (class "Default")
      (node (ref "D5") (pin "5") (pinfunction "IO4_5") (pintype "bidirectional"))
      (node (ref "D5") (pin "6") (pinfunction "NC_6") (pintype "passive"))
      (node (ref "J1") (pin "192") (pinfunction "192_192") (pintype "passive"))
    )
    (net (code "45") (name "/GBE_MDI2_N") (class "Default")
      (node (ref "D12") (pin "1") (pinfunction "IO1_1") (pintype "bidirectional"))
      (node (ref "D12") (pin "10") (pinfunction "NC_10") (pintype "passive"))
      (node (ref "J1") (pin "196") (pinfunction "196_196") (pintype "passive"))
    )
    (net (code "46") (name "/GBE_MDI2_P") (class "Default")
      (node (ref "D12") (pin "2") (pinfunction "IO2_2") (pintype "bidirectional"))
      (node (ref "D12") (pin "9") (pinfunction "NC_9") (pintype "passive"))
      (node (ref "J1") (pin "198") (pinfunction "198_198") (pintype "passive"))
    )
    (net (code "47") (name "/GBE_MDI3_N") (class "Default")
      (node (ref "D12") (pin "4") (pinfunction "IO3_4") (pintype "bidirectional"))
      (node (ref "D12") (pin "7") (pinfunction "NC_7") (pintype "passive"))
      (node (ref "J1") (pin "202") (pinfunction "202_202") (pintype "passive"))
    )
    (net (code "48") (name "/GBE_MDI3_P") (class "Default")
      (node (ref "D12") (pin "5") (pinfunction "IO4_5") (pintype "bidirectional"))
      (node (ref "D12") (pin "6") (pinfunction "NC_6") (pintype "passive"))
      (node (ref "J1") (pin "204") (pinfunction "204_204") (pintype "passive"))
    )
    (net (code "49") (name "/GPIO08_FAN_TACH") (class "Default")
      (node (ref "J1") (pin "208") (pinfunction "208_208") (pintype "passive"))
    )
    (net (code "50") (name "/GPIO09_AUD_MCLK") (class "Default")
      (node (ref "J1") (pin "211") (pinfunction "211_211") (pintype "passive"))
    )
    (net (code "51") (name "/GPIO14_FAN_PWM") (class "Default")
      (node (ref "J1") (pin "230") (pinfunction "230_230") (pintype "passive"))
    )
    (net (code "52") (name "/I2C0_SCL") (class "Default")
      (node (ref "D2") (pin "4") (pinfunction "IO3_4") (pintype "bidirectional"))
      (node (ref "D2") (pin "7") (pinfunction "NC_7") (pintype "passive"))
      (node (ref "J1") (pin "185") (pinfunction "185_185") (pintype "passive"))
    )
    (net (code "53") (name "/I2C0_SDA") (class "Default")
      (node (ref "D2") (pin "5") (pinfunction "IO4_5") (pintype "bidirectional"))
      (node (ref "D2") (pin "6") (pinfunction "NC_6") (pintype "passive"))
      (node (ref "J1") (pin "187") (pinfunction "187_187") (pintype "passive"))
    )
    (net (code "54") (name "/I2S0_DIN") (class "Default")
      (node (ref "D4") (pin "2") (pinfunction "IO2_2") (pintype "bidirectional"))
      (node (ref "D4") (pin "9") (pinfunction "NC_9") (pintype "passive"))
      (node (ref "J1") (pin "195") (pinfunction "195_195") (pintype "passive"))
    )
    (net (code "55") (name "/I2S0_DOUT") (class "Default")
      (node (ref "D4") (pin "1") (pinfunction "IO1_1") (pintype "bidirectional"))
      (node (ref "D4") (pin "10") (pinfunction "NC_10") (pintype "passive"))
      (node (ref "J1") (pin "193") (pinfunction "193_193") (pintype "passive"))
    )
    (net (code "56") (name "/I2S0_FS") (class "Default")
      (node (ref "D4") (pin "4") (pinfunction "IO3_4") (pintype "bidirectional"))
      (node (ref "D4") (pin "7") (pinfunction "NC_7") (pintype "passive"))
      (node (ref "J1") (pin "197") (pinfunction "197_197") (pintype "passive"))
    )
    (net (code "57") (name "/I2S0_SCLK") (class "Default")
      (node (ref "D4") (pin "5") (pinfunction "IO4_5") (pintype "bidirectional"))
      (node (ref "D4") (pin "6") (pinfunction "NC_6") (pintype "passive"))
      (node (ref "J1") (pin "199") (pinfunction "199_199") (pintype "passive"))
    )
    (net (code "58") (name "/PCIE0_CLK_N") (class "Default")
      (node (ref "D18") (pin "1") (pinfunction "IO1_1") (pintype "bidirectional"))
      (node (ref "D18") (pin "10") (pinfunction "NC_10") (pintype "passive"))
      (node (ref "J1") (pin "160") (pinfunction "160_160") (pintype "passive"))
    )
    (net (code "59") (name "/PCIE0_CLK_P") (class "Default")
      (node (ref "D18") (pin "2") (pinfunction "IO2_2") (pintype "bidirectional"))
      (node (ref "D18") (pin "9") (pinfunction "NC_9") (pintype "passive"))
      (node (ref "J1") (pin "162") (pinfunction "162_162") (pintype "passive"))
    )
    (net (code "60") (name "/PCIE0_RX0_N") (class "Default")
      (node (ref "D10") (pin "1") (pinfunction "IO1_1") (pintype "bidirectional"))
      (node (ref "D10") (pin "10") (pinfunction "NC_10") (pintype "passive"))
      (node (ref "J1") (pin "131") (pinfunction "131_131") (pintype "passive"))
    )
    (net (code "61") (name "/PCIE0_RX0_P") (class "Default")
      (node (ref "D10") (pin "2") (pinfunction "IO2_2") (pintype "bidirectional"))
      (node (ref "D10") (pin "9") (pinfunction "NC_9") (pintype "passive"))
      (node (ref "J1") (pin "133") (pinfunction "133_133") (pintype "passive"))
    )
    (net (code "62") (name "/PCIE0_RX1_N") (class "Default")
      (node (ref "D10") (pin "4") (pinfunction "IO3_4") (pintype "bidirectional"))
      (node (ref "D10") (pin "7") (pinfunction "NC_7") (pintype "passive"))
      (node (ref "J1") (pin "137") (pinfunction "137_137") (pintype "passive"))
    )
    (net (code "63") (name "/PCIE0_RX1_P") (class "Default")
      (node (ref "D10") (pin "5") (pinfunction "IO4_5") (pintype "bidirectional"))
      (node (ref "D10") (pin "6") (pinfunction "NC_6") (pintype "passive"))
      (node (ref "J1") (pin "139") (pinfunction "139_139") (pintype "passive"))
    )
    (net (code "64") (name "/PCIE0_RX2_N") (class "Default")
      (node (ref "D17") (pin "1") (pinfunction "IO1_1") (pintype "bidirectional"))
      (node (ref "D17") (pin "10") (pinfunction "NC_10") (pintype "passive"))
      (node (ref "J1") (pin "149") (pinfunction "149_149") (pintype "passive"))
    )
    (net (code "65") (name "/PCIE0_RX2_P") (class "Default")
      (node (ref "D17") (pin "2") (pinfunction "IO2_2") (pintype "bidirectional"))
      (node (ref "D17") (pin "9") (pinfunction "NC_9") (pintype "passive"))
      (node (ref "J1") (pin "151") (pinfunction "151_151") (pintype "passive"))
    )
    (net (code "66") (name "/PCIE0_RX3_N") (class "Default")
      (node (ref "D17") (pin "4") (pinfunction "IO3_4") (pintype "bidirectional"))
      (node (ref "D17") (pin "7") (pinfunction "NC_7") (pintype "passive"))
      (node (ref "J1") (pin "155") (pinfunction "155_155") (pintype "passive"))
    )
    (net (code "67") (name "/PCIE0_RX3_P") (class "Default")
      (node (ref "D17") (pin "5") (pinfunction "IO4_5") (pintype "bidirectional"))
      (node (ref "D17") (pin "6") (pinfunction "NC_6") (pintype "passive"))
      (node (ref "J1") (pin "157") (pinfunction "157_157") (pintype "passive"))
    )
    (net (code "68") (name "/PCIE0_TX0_N") (class "Default")
      (node (ref "D21") (pin "1") (pinfunction "IO1_1") (pintype "bidirectional"))
      (node (ref "D21") (pin "10") (pinfunction "NC_10") (pintype "passive"))
      (node (ref "J1") (pin "134") (pinfunction "134_134") (pintype "passive"))
    )
    (net (code "69") (name "/PCIE0_TX0_P") (class "Default")
      (node (ref "D21") (pin "2") (pinfunction "IO2_2") (pintype "bidirectional"))
      (node (ref "D21") (pin "9") (pinfunction "NC_9") (pintype "passive"))
      (node (ref "J1") (pin "136") (pinfunction "136_136") (pintype "passive"))
    )
    (net (code "70") (name "/PCIE0_TX1_N") (class "Default")
      (node (ref "D21") (pin "4") (pinfunction "IO3_4") (pintype "bidirectional"))
      (node (ref "D21") (pin "7") (pinfunction "NC_7") (pintype "passive"))
      (node (ref "J1") (pin "140") (pinfunction "140_140") (pintype "passive"))
    )
    (net (code "71") (name "/PCIE0_TX1_P") (class "Default")
      (node (ref "D21") (pin "5") (pinfunction "IO4_5") (pintype "bidirectional"))
      (node (ref "D21") (pin "6") (pinfunction "NC_6") (pintype "passive"))
      (node (ref "J1") (pin "142") (pinfunction "142_142") (pintype "passive"))
    )
    (net (code "72") (name "/PCIE0_TX2_N") (class "Default")
      (node (ref "D11") (pin "1") (pinfunction "IO1_1") (pintype "bidirectional"))
      (node (ref "D11") (pin "10") (pinfunction "NC_10") (pintype "passive"))
      (node (ref "J1") (pin "148") (pinfunction "148_148") (pintype "passive"))
    )
    (net (code "73") (name "/PCIE0_TX2_P") (class "Default")
      (node (ref "D11") (pin "2") (pinfunction "IO2_2") (pintype "bidirectional"))
      (node (ref "D11") (pin "9") (pinfunction "NC_9") (pintype "passive"))
      (node (ref "J1") (pin "150") (pinfunction "150_150") (pintype "passive"))
    )
    (net (code "74") (name "/PCIE0_TX3_N") (class "Default")
      (node (ref "D11") (pin "4") (pinfunction "IO3_4") (pintype "bidirectional"))
      (node (ref "D11") (pin "7") (pinfunction "NC_7") (pintype "passive"))
      (node (ref "J1") (pin "154") (pinfunction "154_154") (pintype "passive"))
    )
    (net (code "75") (name "/PCIE0_TX3_P") (class "Default")
      (node (ref "D11") (pin "5") (pinfunction "IO4_5") (pintype "bidirectional"))
      (node (ref "D11") (pin "6") (pinfunction "NC_6") (pintype "passive"))
      (node (ref "J1") (pin "156") (pinfunction "156_156") (pintype "passive"))
    )
    (net (code "76") (name "/PCIE0_nCLKREQ") (class "Default")
      (node (ref "J1") (pin "180") (pinfunction "180_180") (pintype "passive"))
    )
    (net (code "77") (name "/PCIE0_nRST") (class "Default")
      (node (ref "D2") (pin "2") (pinfunction "IO2_2") (pintype "bidirectional"))
      (node (ref "D2") (pin "9") (pinfunction "NC_9") (pintype "passive"))
      (node (ref "J1") (pin "181") (pinfunction "181_181") (pintype "passive"))
    )
    (net (code "78") (name "/PCIE_32K_CLK") (class "Default")
      (node (ref "J1") (pin "210") (pinfunction "210_210") (pintype "passive"))
    )
    (net (code "79") (name "/PCIE_WAKE") (class "Default")
      (node (ref "D2") (pin "1") (pinfunction "IO1_1") (pintype "bidirectional"))
      (node (ref "D2") (pin "10") (pinfunction "NC_10") (pintype "passive"))
      (node (ref "J1") (pin "179") (pinfunction "179_179") (pintype "passive"))
    )
    (net (code "80") (name "/POWER_EN") (class "Default")
      (node (ref "J1") (pin "237") (pinfunction "237_237") (pintype "passive"))
    )
    (net (code "81") (name "/PRE_CSI0_D1_N") (class "Default")
      (node (ref "D13") (pin "1") (pinfunction "IO1_1") (pintype "bidirectional"))
      (node (ref "D13") (pin "10") (pinfunction "NC_10") (pintype "passive"))
      (node (ref "J1") (pin "16") (pinfunction "16_16") (pintype "passive"))
      (node (ref "R3") (pin "1") (pinfunction "1_1") (pintype "passive"))
    )
    (net (code "82") (name "/PRE_CSI0_D1_P") (class "Default")
      (node (ref "D13") (pin "2") (pinfunction "IO2_2") (pintype "bidirectional"))
      (node (ref "D13") (pin "9") (pinfunction "NC_9") (pintype "passive"))
      (node (ref "J1") (pin "18") (pinfunction "18_18") (pintype "passive"))
      (node (ref "R4") (pin "1") (pinfunction "1_1") (pintype "passive"))
    )
    (net (code "83") (name "/PRE_CSI1_D0_N") (class "Default")
      (node (ref "D7") (pin "1") (pinfunction "IO1_1") (pintype "bidirectional"))
      (node (ref "D7") (pin "10") (pinfunction "NC_10") (pintype "passive"))
      (node (ref "J1") (pin "3") (pinfunction "3_3") (pintype "passive"))
      (node (ref "R1") (pin "1") (pinfunction "1_1") (pintype "passive"))
    )
    (net (code "84") (name "/PRE_CSI1_D0_P") (class "Default")
      (node (ref "D7") (pin "2") (pinfunction "IO2_2") (pintype "bidirectional"))
      (node (ref "D7") (pin "9") (pinfunction "NC_9") (pintype "passive"))
      (node (ref "J1") (pin "5") (pinfunction "5_5") (pintype "passive"))
      (node (ref "R2") (pin "1") (pinfunction "1_1") (pintype "passive"))
    )
    (net (code "85") (name "/REC_USB_VBUS") (class "Default")
      (node (ref "Q6") (pin "1") (pinfunction "G_1") (pintype "passive"))
      (node (ref "R22") (pin "2") (pinfunction "2_2") (pintype "passive"))
    )
    (net (code "86") (name "/SPI0_MISO") (class "Default")
      (node (ref "D1") (pin "4") (pinfunction "IO3_4") (pintype "bidirectional"))
      (node (ref "D1") (pin "7") (pinfunction "NC_7") (pintype "passive"))
      (node (ref "J1") (pin "93") (pinfunction "93_93") (pintype "passive"))
    )
    (net (code "87") (name "/SPI0_MOSI") (class "Default")
      (node (ref "D1") (pin "1") (pinfunction "IO1_1") (pintype "bidirectional"))
      (node (ref "D1") (pin "10") (pinfunction "NC_10") (pintype "passive"))
      (node (ref "J1") (pin "89") (pinfunction "89_89") (pintype "passive"))
    )
    (net (code "88") (name "/SPI0_SCLK") (class "Default")
      (node (ref "D1") (pin "2") (pinfunction "IO2_2") (pintype "bidirectional"))
      (node (ref "D1") (pin "9") (pinfunction "NC_9") (pintype "passive"))
      (node (ref "J1") (pin "91") (pinfunction "91_91") (pintype "passive"))
    )
    (net (code "89") (name "/SPI0_nCS_0") (class "Default")
      (node (ref "D1") (pin "5") (pinfunction "IO4_5") (pintype "bidirectional"))
      (node (ref "D1") (pin "6") (pinfunction "NC_6") (pintype "passive"))
      (node (ref "J1") (pin "95") (pinfunction "95_95") (pintype "passive"))
    )
    (net (code "90") (name "/SPI0_nCS_1") (class "Default")
      (node (ref "J1") (pin "97") (pinfunction "97_97") (pintype "passive"))
    )
    (net (code "91") (name "/SPI1_MISO") (class "Default")
      (node (ref "D3") (pin "4") (pinfunction "IO3_4") (pintype "bidirectional"))
      (node (ref "D3") (pin "7") (pinfunction "NC_7") (pintype "passive"))
      (node (ref "J1") (pin "108") (pinfunction "108_108") (pintype "passive"))
    )
    (net (code "92") (name "/SPI1_MOSI") (class "Default")
      (node (ref "D3") (pin "1") (pinfunction "IO1_1") (pintype "bidirectional"))
      (node (ref "D3") (pin "10") (pinfunction "NC_10") (pintype "passive"))
      (node (ref "J1") (pin "104") (pinfunction "104_104") (pintype "passive"))
    )
    (net (code "93") (name "/SPI1_SCLK") (class "Default")
      (node (ref "D3") (pin "2") (pinfunction "IO2_2") (pintype "bidirectional"))
      (node (ref "D3") (pin "9") (pinfunction "NC_9") (pintype "passive"))
      (node (ref "J1") (pin "106") (pinfunction "106_106") (pintype "passive"))
    )
    (net (code "94") (name "/SPI1_nCS_0") (class "Default")
      (node (ref "D3") (pin "5") (pinfunction "IO4_5") (pintype "bidirectional"))
      (node (ref "D3") (pin "6") (pinfunction "NC_6") (pintype "passive"))
      (node (ref "J1") (pin "110") (pinfunction "110_110") (pintype "passive"))
    )
    (net (code "95") (name "/SPI1_nCS_1") (class "Default")
      (node (ref "J1") (pin "112") (pinfunction "112_112") (pintype "passive"))
    )
    (net (code "96") (name "/USB0_D_N") (class "Default")
      (node (ref "D9") (pin "1") (pinfunction "IO1_1") (pintype "bidirectional"))
      (node (ref "D9") (pin "10") (pinfunction "NC_10") (pintype "passive"))
      (node (ref "J1") (pin "109") (pinfunction "109_109") (pintype "passive"))
    )
    (net (code "97") (name "/USB0_D_P") (class "Default")
      (node (ref "D9") (pin "2") (pinfunction "IO2_2") (pintype "bidirectional"))
      (node (ref "D9") (pin "9") (pinfunction "NC_9") (pintype "passive"))
      (node (ref "J1") (pin "111") (pinfunction "111_111") (pintype "passive"))
    )
    (net (code "98") (name "/USB1_D_N") (class "Default")
      (node (ref "D9") (pin "4") (pinfunction "IO3_4") (pintype "bidirectional"))
      (node (ref "D9") (pin "7") (pinfunction "NC_7") (pintype "passive"))
      (node (ref "J1") (pin "115") (pinfunction "115_115") (pintype "passive"))
    )
    (net (code "99") (name "/USB1_D_P") (class "Default")
      (node (ref "D9") (pin "5") (pinfunction "IO4_5") (pintype "bidirectional"))
      (node (ref "D9") (pin "6") (pinfunction "NC_6") (pintype "passive"))
      (node (ref "J1") (pin "117") (pinfunction "117_117") (pintype "passive"))
    )
    (net (code "100") (name "/USBSS0_RX_N") (class "Default")
      (node (ref "D16") (pin "1") (pinfunction "IO1_1") (pintype "bidirectional"))
      (node (ref "D16") (pin "10") (pinfunction "NC_10") (pintype "passive"))
      (node (ref "J1") (pin "161") (pinfunction "161_161") (pintype "passive"))
    )
    (net (code "101") (name "/USBSS0_RX_P") (class "Default")
      (node (ref "D16") (pin "2") (pinfunction "IO2_2") (pintype "bidirectional"))
      (node (ref "D16") (pin "9") (pinfunction "NC_9") (pintype "passive"))
      (node (ref "J1") (pin "163") (pinfunction "163_163") (pintype "passive"))
    )
    (net (code "102") (name "/USBSS0_TX_N") (class "Default")
      (node (ref "D16") (pin "4") (pinfunction "IO3_4") (pintype "bidirectional"))
      (node (ref "D16") (pin "7") (pinfunction "NC_7") (pintype "passive"))
      (node (ref "J1") (pin "166") (pinfunction "166_166") (pintype "passive"))
    )
    (net (code "103") (name "/USBSS0_TX_P") (class "Default")
      (node (ref "D16") (pin "5") (pinfunction "IO4_5") (pintype "bidirectional"))
      (node (ref "D16") (pin "6") (pinfunction "NC_6") (pintype "passive"))
      (node (ref "J1") (pin "168") (pinfunction "168_168") (pintype "passive"))
    )
    (net (code "104") (name "/VBUS_DETECT") (class "Default")
      (node (ref "J1") (pin "87") (pinfunction "87_87") (pintype "passive"))
      (node (ref "R23") (pin "2") (pinfunction "2_2") (pintype "passive"))
    )
    (net (code "105") (name "/nFORCE_RECOVERY") (class "Default")
      (node (ref "J1") (pin "214") (pinfunction "214_214") (pintype "passive"))
    )
    (net (code "106") (name "/nMOD_SLEEP") (class "Default")
      (node (ref "J1") (pin "178") (pinfunction "178_178") (pintype "passive"))
    )
    (net (code "107") (name "/nSHUTDOWN_REQ") (class "Default")
      (node (ref "J1") (pin "233") (pinfunction "233_233") (pintype "passive"))
    )
    (net (code "108") (name "/nSYS_RESET") (class "Default")
      (node (ref "J1") (pin "239") (pinfunction "239_239") (pintype "passive"))
    )
    (net (code "109") (name "5V_MAIN") (class "Default")
      (node (ref "J1") (pin "251") (pinfunction "251_251") (pintype "passive"))
      (node (ref "J1") (pin "252") (pinfunction "252_252") (pintype "passive"))
      (node (ref "J1") (pin "253") (pinfunction "253_253") (pintype "passive"))
      (node (ref "J1") (pin "254") (pinfunction "254_254") (pintype "passive"))
      (node (ref "J1") (pin "255") (pinfunction "255_255") (pintype "passive"))
      (node (ref "J1") (pin "256") (pinfunction "256_256") (pintype "passive"))
      (node (ref "J1") (pin "257") (pinfunction "257_257") (pintype "passive"))
      (node (ref "J1") (pin "258") (pinfunction "258_258") (pintype "passive"))
      (node (ref "J1") (pin "259") (pinfunction "259_259") (pintype "passive"))
      (node (ref "J1") (pin "260") (pinfunction "260_260") (pintype "passive"))
    )
    (net (code "110") (name "GND") (class "Default")
      (node (ref "D1") (pin "3") (pinfunction "GND_3") (pintype "power_in"))
      (node (ref "D1") (pin "8") (pinfunction "GND_8") (pintype "power_in"))
      (node (ref "D10") (pin "3") (pinfunction "GND_3") (pintype "power_in"))
      (node (ref "D10") (pin "8") (pinfunction "GND_8") (pintype "power_in"))
      (node (ref "D11") (pin "3") (pinfunction "GND_3") (pintype "power_in"))
      (node (ref "D11") (pin "8") (pinfunction "GND_8") (pintype "power_in"))
      (node (ref "D12") (pin "3") (pinfunction "GND_3") (pintype "power_in"))
      (node (ref "D12") (pin "8") (pinfunction "GND_8") (pintype "power_in"))
      (node (ref "D13") (pin "3") (pinfunction "GND_3") (pintype "power_in"))
      (node (ref "D13") (pin "8") (pinfunction "GND_8") (pintype "power_in"))
      (node (ref "D14") (pin "3") (pinfunction "GND_3") (pintype "power_in"))
      (node (ref "D14") (pin "8") (pinfunction "GND_8") (pintype "power_in"))
      (node (ref "D15") (pin "3") (pinfunction "GND_3") (pintype "power_in"))
      (node (ref "D15") (pin "8") (pinfunction "GND_8") (pintype "power_in"))
      (node (ref "D16") (pin "3") (pinfunction "GND_3") (pintype "power_in"))
      (node (ref "D16") (pin "8") (pinfunction "GND_8") (pintype "power_in"))
      (node (ref "D17") (pin "3") (pinfunction "GND_3") (pintype "power_in"))
      (node (ref "D17") (pin "8") (pinfunction "GND_8") (pintype "power_in"))
      (node (ref "D18") (pin "3") (pinfunction "GND_3") (pintype "power_in"))
      (node (ref "D18") (pin "8") (pinfunction "GND_8") (pintype "power_in"))
      (node (ref "D19") (pin "3") (pinfunction "GND_3") (pintype "power_in"))
      (node (ref "D19") (pin "8") (pinfunction "GND_8") (pintype "power_in"))
      (node (ref "D2") (pin "3") (pinfunction "GND_3") (pintype "power_in"))
      (node (ref "D2") (pin "8") (pinfunction "GND_8") (pintype "power_in"))
      (node (ref "D20") (pin "3") (pinfunction "GND_3") (pintype "power_in"))
      (node (ref "D20") (pin "8") (pinfunction "GND_8") (pintype "power_in"))
      (node (ref "D21") (pin "3") (pinfunction "GND_3") (pintype "power_in"))
      (node (ref "D21") (pin "8") (pinfunction "GND_8") (pintype "power_in"))
      (node (ref "D3") (pin "3") (pinfunction "GND_3") (pintype "power_in"))
      (node (ref "D3") (pin "8") (pinfunction "GND_8") (pintype "power_in"))
      (node (ref "D4") (pin "3") (pinfunction "GND_3") (pintype "power_in"))
      (node (ref "D4") (pin "8") (pinfunction "GND_8") (pintype "power_in"))
      (node (ref "D5") (pin "3") (pinfunction "GND_3") (pintype "power_in"))
      (node (ref "D5") (pin "8") (pinfunction "GND_8") (pintype "power_in"))
      (node (ref "D6") (pin "3") (pinfunction "GND_3") (pintype "power_in"))
      (node (ref "D6") (pin "8") (pinfunction "GND_8") (pintype "power_in"))
      (node (ref "D7") (pin "3") (pinfunction "GND_3") (pintype "power_in"))
      (node (ref "D7") (pin "8") (pinfunction "GND_8") (pintype "power_in"))
      (node (ref "D8") (pin "3") (pinfunction "GND_3") (pintype "power_in"))
      (node (ref "D8") (pin "8") (pinfunction "GND_8") (pintype "power_in"))
      (node (ref "D9") (pin "3") (pinfunction "GND_3") (pintype "power_in"))
      (node (ref "D9") (pin "8") (pinfunction "GND_8") (pintype "power_in"))
      (node (ref "J1") (pin "1") (pinfunction "1_1") (pintype "passive"))
      (node (ref "J1") (pin "102") (pinfunction "102_102") (pintype "passive"))
      (node (ref "J1") (pin "107") (pinfunction "107_107") (pintype "passive"))
      (node (ref "J1") (pin "113") (pinfunction "113_113") (pintype "passive"))
      (node (ref "J1") (pin "119") (pinfunction "119_119") (pintype "passive"))
      (node (ref "J1") (pin "125") (pinfunction "125_125") (pintype "passive"))
      (node (ref "J1") (pin "129") (pinfunction "129_129") (pintype "passive"))
      (node (ref "J1") (pin "13") (pinfunction "13_13") (pintype "passive"))
      (node (ref "J1") (pin "132") (pinfunction "132_132") (pintype "passive"))
      (node (ref "J1") (pin "135") (pinfunction "135_135") (pintype "passive"))
      (node (ref "J1") (pin "138") (pinfunction "138_138") (pintype "passive"))
      (node (ref "J1") (pin "14") (pinfunction "14_14") (pintype "passive"))
      (node (ref "J1") (pin "141") (pinfunction "141_141") (pintype "passive"))
      (node (ref "J1") (pin "144") (pinfunction "144_144") (pintype "passive"))
      (node (ref "J1") (pin "146") (pinfunction "146_146") (pintype "passive"))
      (node (ref "J1") (pin "147") (pinfunction "147_147") (pintype "passive"))
      (node (ref "J1") (pin "152") (pinfunction "152_152") (pintype "passive"))
      (node (ref "J1") (pin "153") (pinfunction "153_153") (pintype "passive"))
      (node (ref "J1") (pin "158") (pinfunction "158_158") (pintype "passive"))
      (node (ref "J1") (pin "159") (pinfunction "159_159") (pintype "passive"))
      (node (ref "J1") (pin "164") (pinfunction "164_164") (pintype "passive"))
      (node (ref "J1") (pin "165") (pinfunction "165_165") (pintype "passive"))
      (node (ref "J1") (pin "170") (pinfunction "170_170") (pintype "passive"))
      (node (ref "J1") (pin "171") (pinfunction "171_171") (pintype "passive"))
      (node (ref "J1") (pin "176") (pinfunction "176_176") (pintype "passive"))
      (node (ref "J1") (pin "177") (pinfunction "177_177") (pintype "passive"))
      (node (ref "J1") (pin "19") (pinfunction "19_19") (pintype "passive"))
      (node (ref "J1") (pin "2") (pinfunction "2_2") (pintype "passive"))
      (node (ref "J1") (pin "20") (pinfunction "20_20") (pintype "passive"))
      (node (ref "J1") (pin "200") (pinfunction "200_200") (pintype "passive"))
      (node (ref "J1") (pin "201") (pinfunction "201_201") (pintype "passive"))
      (node (ref "J1") (pin "231") (pinfunction "231_231") (pintype "passive"))
      (node (ref "J1") (pin "241") (pinfunction "241_241") (pintype "passive"))
      (node (ref "J1") (pin "242") (pinfunction "242_242") (pintype "passive"))
      (node (ref "J1") (pin "243") (pinfunction "243_243") (pintype "passive"))
      (node (ref "J1") (pin "244") (pinfunction "244_244") (pintype "passive"))
      (node (ref "J1") (pin "245") (pinfunction "245_245") (pintype "passive"))
      (node (ref "J1") (pin "246") (pinfunction "246_246") (pintype "passive"))
      (node (ref "J1") (pin "247") (pinfunction "247_247") (pintype "passive"))
      (node (ref "J1") (pin "248") (pinfunction "248_248") (pintype "passive"))
      (node (ref "J1") (pin "249") (pinfunction "249_249") (pintype "passive"))
      (node (ref "J1") (pin "25") (pinfunction "25_25") (pintype "passive"))
      (node (ref "J1") (pin "250") (pinfunction "250_250") (pintype "passive"))
      (node (ref "J1") (pin "26") (pinfunction "26_26") (pintype "passive"))
      (node (ref "J1") (pin "261") (pinfunction "MNT_1_261") (pintype "passive"))
      (node (ref "J1") (pin "262") (pinfunction "MNT_2_262") (pintype "passive"))
      (node (ref "J1") (pin "31") (pinfunction "31_31") (pintype "passive"))
      (node (ref "J1") (pin "32") (pinfunction "32_32") (pintype "passive"))
      (node (ref "J1") (pin "37") (pinfunction "37_37") (pintype "passive"))
      (node (ref "J1") (pin "38") (pinfunction "38_38") (pintype "passive"))
      (node (ref "J1") (pin "43") (pinfunction "43_43") (pintype "passive"))
      (node (ref "J1") (pin "44") (pinfunction "44_44") (pintype "passive"))
      (node (ref "J1") (pin "49") (pinfunction "49_49") (pintype "passive"))
      (node (ref "J1") (pin "50") (pinfunction "50_50") (pintype "passive"))
      (node (ref "J1") (pin "55") (pinfunction "55_55") (pintype "passive"))
      (node (ref "J1") (pin "56") (pinfunction "56_56") (pintype "passive"))
      (node (ref "J1") (pin "61") (pinfunction "61_61") (pintype "passive"))
      (node (ref "J1") (pin "62") (pinfunction "62_62") (pintype "passive"))
      (node (ref "J1") (pin "67") (pinfunction "67_67") (pintype "passive"))
      (node (ref "J1") (pin "68") (pinfunction "68_68") (pintype "passive"))
      (node (ref "J1") (pin "7") (pinfunction "7_7") (pintype "passive"))
      (node (ref "J1") (pin "73") (pinfunction "73_73") (pintype "passive"))
      (node (ref "J1") (pin "74") (pinfunction "74_74") (pintype "passive"))
      (node (ref "J1") (pin "79") (pinfunction "79_79") (pintype "passive"))
      (node (ref "J1") (pin "8") (pinfunction "8_8") (pintype "passive"))
      (node (ref "J1") (pin "80") (pinfunction "80_80") (pintype "passive"))
      (node (ref "J1") (pin "85") (pinfunction "85_85") (pintype "passive"))
      (node (ref "J1") (pin "86") (pinfunction "86_86") (pintype "passive"))
      (node (ref "MP2") (pin "1") (pinfunction "1_1") (pintype "passive"))
      (node (ref "MP3") (pin "1") (pinfunction "1_1") (pintype "passive"))
      (node (ref "Q6") (pin "2") (pinfunction "S_2") (pintype "passive"))
      (node (ref "R22") (pin "1") (pinfunction "1_1") (pintype "passive"))
    )
    (net (code "111") (name "Net-(Q6-D)") (class "Default")
      (node (ref "Q6") (pin "3") (pinfunction "D_3") (pintype "passive"))
      (node (ref "R23") (pin "1") (pinfunction "1_1") (pintype "passive"))
    )
    (net (code "112") (name "unconnected-(J1-Pad9)") (class "Default")
      (node (ref "J1") (pin "9") (pinfunction "9_9") (pintype "passive+no_connect"))
    )
    (net (code "113") (name "unconnected-(J1-Pad11)") (class "Default")
      (node (ref "J1") (pin "11") (pinfunction "11_11") (pintype "passive+no_connect"))
    )
    (net (code "114") (name "unconnected-(J1-Pad27)") (class "Default")
      (node (ref "J1") (pin "27") (pinfunction "27_27") (pintype "passive+no_connect"))
    )
    (net (code "115") (name "unconnected-(J1-Pad29)") (class "Default")
      (node (ref "J1") (pin "29") (pinfunction "29_29") (pintype "passive+no_connect"))
    )
    (net (code "116") (name "unconnected-(J1-Pad39)") (class "Default")
      (node (ref "J1") (pin "39") (pinfunction "39_39") (pintype "passive+no_connect"))
    )
    (net (code "117") (name "unconnected-(J1-Pad40)") (class "Default")
      (node (ref "J1") (pin "40") (pinfunction "40_40") (pintype "passive+no_connect"))
    )
    (net (code "118") (name "unconnected-(J1-Pad41)") (class "Default")
      (node (ref "J1") (pin "41") (pinfunction "41_41") (pintype "passive+no_connect"))
    )
    (net (code "119") (name "unconnected-(J1-Pad42)") (class "Default")
      (node (ref "J1") (pin "42") (pinfunction "42_42") (pintype "passive+no_connect"))
    )
    (net (code "120") (name "unconnected-(J1-Pad45)") (class "Default")
      (node (ref "J1") (pin "45") (pinfunction "45_45") (pintype "passive+no_connect"))
    )
    (net (code "121") (name "unconnected-(J1-Pad46)") (class "Default")
      (node (ref "J1") (pin "46") (pinfunction "46_46") (pintype "passive+no_connect"))
    )
    (net (code "122") (name "unconnected-(J1-Pad47)") (class "Default")
      (node (ref "J1") (pin "47") (pinfunction "47_47") (pintype "passive+no_connect"))
    )
    (net (code "123") (name "unconnected-(J1-Pad48)") (class "Default")
      (node (ref "J1") (pin "48") (pinfunction "48_48") (pintype "passive+no_connect"))
    )
    (net (code "124") (name "unconnected-(J1-Pad51)") (class "Default")
      (node (ref "J1") (pin "51") (pinfunction "51_51") (pintype "passive+no_connect"))
    )
    (net (code "125") (name "unconnected-(J1-Pad52)") (class "Default")
      (node (ref "J1") (pin "52") (pinfunction "52_52") (pintype "passive+no_connect"))
    )
    (net (code "126") (name "unconnected-(J1-Pad53)") (class "Default")
      (node (ref "J1") (pin "53") (pinfunction "53_53") (pintype "passive+no_connect"))
    )
    (net (code "127") (name "unconnected-(J1-Pad54)") (class "Default")
      (node (ref "J1") (pin "54") (pinfunction "54_54") (pintype "passive+no_connect"))
    )
    (net (code "128") (name "unconnected-(J1-Pad57)") (class "Default")
      (node (ref "J1") (pin "57") (pinfunction "57_57") (pintype "passive+no_connect"))
    )
    (net (code "129") (name "unconnected-(J1-Pad58)") (class "Default")
      (node (ref "J1") (pin "58") (pinfunction "58_58") (pintype "passive+no_connect"))
    )
    (net (code "130") (name "unconnected-(J1-Pad59)") (class "Default")
      (node (ref "J1") (pin "59") (pinfunction "59_59") (pintype "passive+no_connect"))
    )
    (net (code "131") (name "unconnected-(J1-Pad60)") (class "Default")
      (node (ref "J1") (pin "60") (pinfunction "60_60") (pintype "passive+no_connect"))
    )
    (net (code "132") (name "unconnected-(J1-Pad64)") (class "Default")
      (node (ref "J1") (pin "64") (pinfunction "64_64") (pintype "passive+no_connect"))
    )
    (net (code "133") (name "unconnected-(J1-Pad66)") (class "Default")
      (node (ref "J1") (pin "66") (pinfunction "66_66") (pintype "passive+no_connect"))
    )
    (net (code "134") (name "unconnected-(J1-Pad70)") (class "Default")
      (node (ref "J1") (pin "70") (pinfunction "70_70") (pintype "passive+no_connect"))
    )
    (net (code "135") (name "unconnected-(J1-Pad72)") (class "Default")
      (node (ref "J1") (pin "72") (pinfunction "72_72") (pintype "passive+no_connect"))
    )
    (net (code "136") (name "unconnected-(J1-Pad76)") (class "Default")
      (node (ref "J1") (pin "76") (pinfunction "76_76") (pintype "passive+no_connect"))
    )
    (net (code "137") (name "unconnected-(J1-Pad78)") (class "Default")
      (node (ref "J1") (pin "78") (pinfunction "78_78") (pintype "passive+no_connect"))
    )
    (net (code "138") (name "unconnected-(J1-Pad82)") (class "Default")
      (node (ref "J1") (pin "82") (pinfunction "82_82") (pintype "passive+no_connect"))
    )
    (net (code "139") (name "unconnected-(J1-Pad84)") (class "Default")
      (node (ref "J1") (pin "84") (pinfunction "84_84") (pintype "passive+no_connect"))
    )
    (net (code "140") (name "unconnected-(J1-Pad88)") (class "Default")
      (node (ref "J1") (pin "88") (pinfunction "88_88") (pintype "passive+no_connect"))
    )
    (net (code "141") (name "unconnected-(J1-Pad90)") (class "Default")
      (node (ref "J1") (pin "90") (pinfunction "90_90") (pintype "passive+no_connect"))
    )
    (net (code "142") (name "unconnected-(J1-Pad92)") (class "Default")
      (node (ref "J1") (pin "92") (pinfunction "92_92") (pintype "passive+no_connect"))
    )
    (net (code "143") (name "unconnected-(J1-Pad99)") (class "Default")
      (node (ref "J1") (pin "99") (pinfunction "99_99") (pintype "passive+no_connect"))
    )
    (net (code "144") (name "unconnected-(J1-Pad101)") (class "Default")
      (node (ref "J1") (pin "101") (pinfunction "101_101") (pintype "passive+no_connect"))
    )
    (net (code "145") (name "unconnected-(J1-Pad103)") (class "Default")
      (node (ref "J1") (pin "103") (pinfunction "103_103") (pintype "passive+no_connect"))
    )
    (net (code "146") (name "unconnected-(J1-Pad105)") (class "Default")
      (node (ref "J1") (pin "105") (pinfunction "105_105") (pintype "passive+no_connect"))
    )
    (net (code "147") (name "unconnected-(J1-Pad114)") (class "Default")
      (node (ref "J1") (pin "114") (pinfunction "114_114") (pintype "passive+no_connect"))
    )
    (net (code "148") (name "unconnected-(J1-Pad118)") (class "Default")
      (node (ref "J1") (pin "118") (pinfunction "118_118") (pintype "passive+no_connect"))
    )
    (net (code "149") (name "unconnected-(J1-Pad121)") (class "Default")
      (node (ref "J1") (pin "121") (pinfunction "121_121") (pintype "passive+no_connect"))
    )
    (net (code "150") (name "unconnected-(J1-Pad122)") (class "Default")
      (node (ref "J1") (pin "122") (pinfunction "122_122") (pintype "passive+no_connect"))
    )
    (net (code "151") (name "unconnected-(J1-Pad123)") (class "Default")
      (node (ref "J1") (pin "123") (pinfunction "123_123") (pintype "passive+no_connect"))
    )
    (net (code "152") (name "unconnected-(J1-Pad124)") (class "Default")
      (node (ref "J1") (pin "124") (pinfunction "124_124") (pintype "passive+no_connect"))
    )
    (net (code "153") (name "unconnected-(J1-Pad126)") (class "Default")
      (node (ref "J1") (pin "126") (pinfunction "126_126") (pintype "passive+no_connect"))
    )
    (net (code "154") (name "unconnected-(J1-Pad127)") (class "Default")
      (node (ref "J1") (pin "127") (pinfunction "127_127") (pintype "passive+no_connect"))
    )
    (net (code "155") (name "unconnected-(J1-Pad128)") (class "Default")
      (node (ref "J1") (pin "128") (pinfunction "128_128") (pintype "passive+no_connect"))
    )
    (net (code "156") (name "unconnected-(J1-Pad130)") (class "Default")
      (node (ref "J1") (pin "130") (pinfunction "130_130") (pintype "passive+no_connect"))
    )
    (net (code "157") (name "unconnected-(J1-Pad167)") (class "Default")
      (node (ref "J1") (pin "167") (pinfunction "167_167") (pintype "passive+no_connect"))
    )
    (net (code "158") (name "unconnected-(J1-Pad169)") (class "Default")
      (node (ref "J1") (pin "169") (pinfunction "169_169") (pintype "passive+no_connect"))
    )
    (net (code "159") (name "unconnected-(J1-Pad172)") (class "Default")
      (node (ref "J1") (pin "172") (pinfunction "172_172") (pintype "passive+no_connect"))
    )
    (net (code "160") (name "unconnected-(J1-Pad173)") (class "Default")
      (node (ref "J1") (pin "173") (pinfunction "173_173") (pintype "passive+no_connect"))
    )
    (net (code "161") (name "unconnected-(J1-Pad174)") (class "Default")
      (node (ref "J1") (pin "174") (pinfunction "174_174") (pintype "passive+no_connect"))
    )
    (net (code "162") (name "unconnected-(J1-Pad175)") (class "Default")
      (node (ref "J1") (pin "175") (pinfunction "175_175") (pintype "passive+no_connect"))
    )
    (net (code "163") (name "unconnected-(J1-Pad182)") (class "Default")
      (node (ref "J1") (pin "182") (pinfunction "182_182") (pintype "passive+no_connect"))
    )
    (net (code "164") (name "unconnected-(J1-Pad183)") (class "Default")
      (node (ref "J1") (pin "183") (pinfunction "183_183") (pintype "passive+no_connect"))
    )
    (net (code "165") (name "unconnected-(J1-Pad189)") (class "Default")
      (node (ref "J1") (pin "189") (pinfunction "189_189") (pintype "passive+no_connect"))
    )
    (net (code "166") (name "unconnected-(J1-Pad191)") (class "Default")
      (node (ref "J1") (pin "191") (pinfunction "191_191") (pintype "passive+no_connect"))
    )
    (net (code "167") (name "unconnected-(J1-Pad203)") (class "Default")
      (node (ref "J1") (pin "203") (pinfunction "203_203") (pintype "passive+no_connect"))
    )
    (net (code "168") (name "unconnected-(J1-Pad205)") (class "Default")
      (node (ref "J1") (pin "205") (pinfunction "205_205") (pintype "passive+no_connect"))
    )
    (net (code "169") (name "unconnected-(J1-Pad206)") (class "Default")
      (node (ref "J1") (pin "206") (pinfunction "206_206") (pintype "passive+no_connect"))
    )
    (net (code "170") (name "unconnected-(J1-Pad207)") (class "Default")
      (node (ref "J1") (pin "207") (pinfunction "207_207") (pintype "passive+no_connect"))
    )
    (net (code "171") (name "unconnected-(J1-Pad209)") (class "Default")
      (node (ref "J1") (pin "209") (pinfunction "209_209") (pintype "passive+no_connect"))
    )
    (net (code "172") (name "unconnected-(J1-Pad212)") (class "Default")
      (node (ref "J1") (pin "212") (pinfunction "212_212") (pintype "passive+no_connect"))
    )
    (net (code "173") (name "unconnected-(J1-Pad216)") (class "Default")
      (node (ref "J1") (pin "216") (pinfunction "216_216") (pintype "passive+no_connect"))
    )
    (net (code "174") (name "unconnected-(J1-Pad217)") (class "Default")
      (node (ref "J1") (pin "217") (pinfunction "217_217") (pintype "passive+no_connect"))
    )
    (net (code "175") (name "unconnected-(J1-Pad218)") (class "Default")
      (node (ref "J1") (pin "218") (pinfunction "218_218") (pintype "passive+no_connect"))
    )
    (net (code "176") (name "unconnected-(J1-Pad219)") (class "Default")
      (node (ref "J1") (pin "219") (pinfunction "219_219") (pintype "passive+no_connect"))
    )
    (net (code "177") (name "unconnected-(J1-Pad220)") (class "Default")
      (node (ref "J1") (pin "220") (pinfunction "220_220") (pintype "passive+no_connect"))
    )
    (net (code "178") (name "unconnected-(J1-Pad221)") (class "Default")
      (node (ref "J1") (pin "221") (pinfunction "221_221") (pintype "passive+no_connect"))
    )
    (net (code "179") (name "unconnected-(J1-Pad222)") (class "Default")
      (node (ref "J1") (pin "222") (pinfunction "222_222") (pintype "passive+no_connect"))
    )
    (net (code "180") (name "unconnected-(J1-Pad223)") (class "Default")
      (node (ref "J1") (pin "223") (pinfunction "223_223") (pintype "passive+no_connect"))
    )
    (net (code "181") (name "unconnected-(J1-Pad224)") (class "Default")
      (node (ref "J1") (pin "224") (pinfunction "224_224") (pintype "passive+no_connect"))
    )
    (net (code "182") (name "unconnected-(J1-Pad225)") (class "Default")
      (node (ref "J1") (pin "225") (pinfunction "225_225") (pintype "passive+no_connect"))
    )
    (net (code "183") (name "unconnected-(J1-Pad226)") (class "Default")
      (node (ref "J1") (pin "226") (pinfunction "226_226") (pintype "passive+no_connect"))
    )
    (net (code "184") (name "unconnected-(J1-Pad227)") (class "Default")
      (node (ref "J1") (pin "227") (pinfunction "227_227") (pintype "passive+no_connect"))
    )
    (net (code "185") (name "unconnected-(J1-Pad228)") (class "Default")
      (node (ref "J1") (pin "228") (pinfunction "228_228") (pintype "passive+no_connect"))
    )
    (net (code "186") (name "unconnected-(J1-Pad229)") (class "Default")
      (node (ref "J1") (pin "229") (pinfunction "229_229") (pintype "passive+no_connect"))
    )
    (net (code "187") (name "unconnected-(J1-Pad232)") (class "Default")
      (node (ref "J1") (pin "232") (pinfunction "232_232") (pintype "passive+no_connect"))
    )
    (net (code "188") (name "unconnected-(J1-Pad234)") (class "Default")
      (node (ref "J1") (pin "234") (pinfunction "234_234") (pintype "passive+no_connect"))
    )
    (net (code "189") (name "unconnected-(J1-Pad235)") (class "Default")
      (node (ref "J1") (pin "235") (pinfunction "235_235") (pintype "passive+no_connect"))
    )
    (net (code "190") (name "unconnected-(J1-Pad236)") (class "Default")
      (node (ref "J1") (pin "236") (pinfunction "236_236") (pintype "passive+no_connect"))
    )
    (net (code "191") (name "unconnected-(J1-Pad238)") (class "Default")
      (node (ref "J1") (pin "238") (pinfunction "238_238") (pintype "passive+no_connect"))
    )
    (net (code "192") (name "unconnected-(J1-Pad240)") (class "Default")
      (node (ref "J1") (pin "240") (pinfunction "240_240") (pintype "passive+no_connect"))
    )
  )
)
